# io-board-e-1.net
KiCad netlist of a schematic drawn in EAGLE
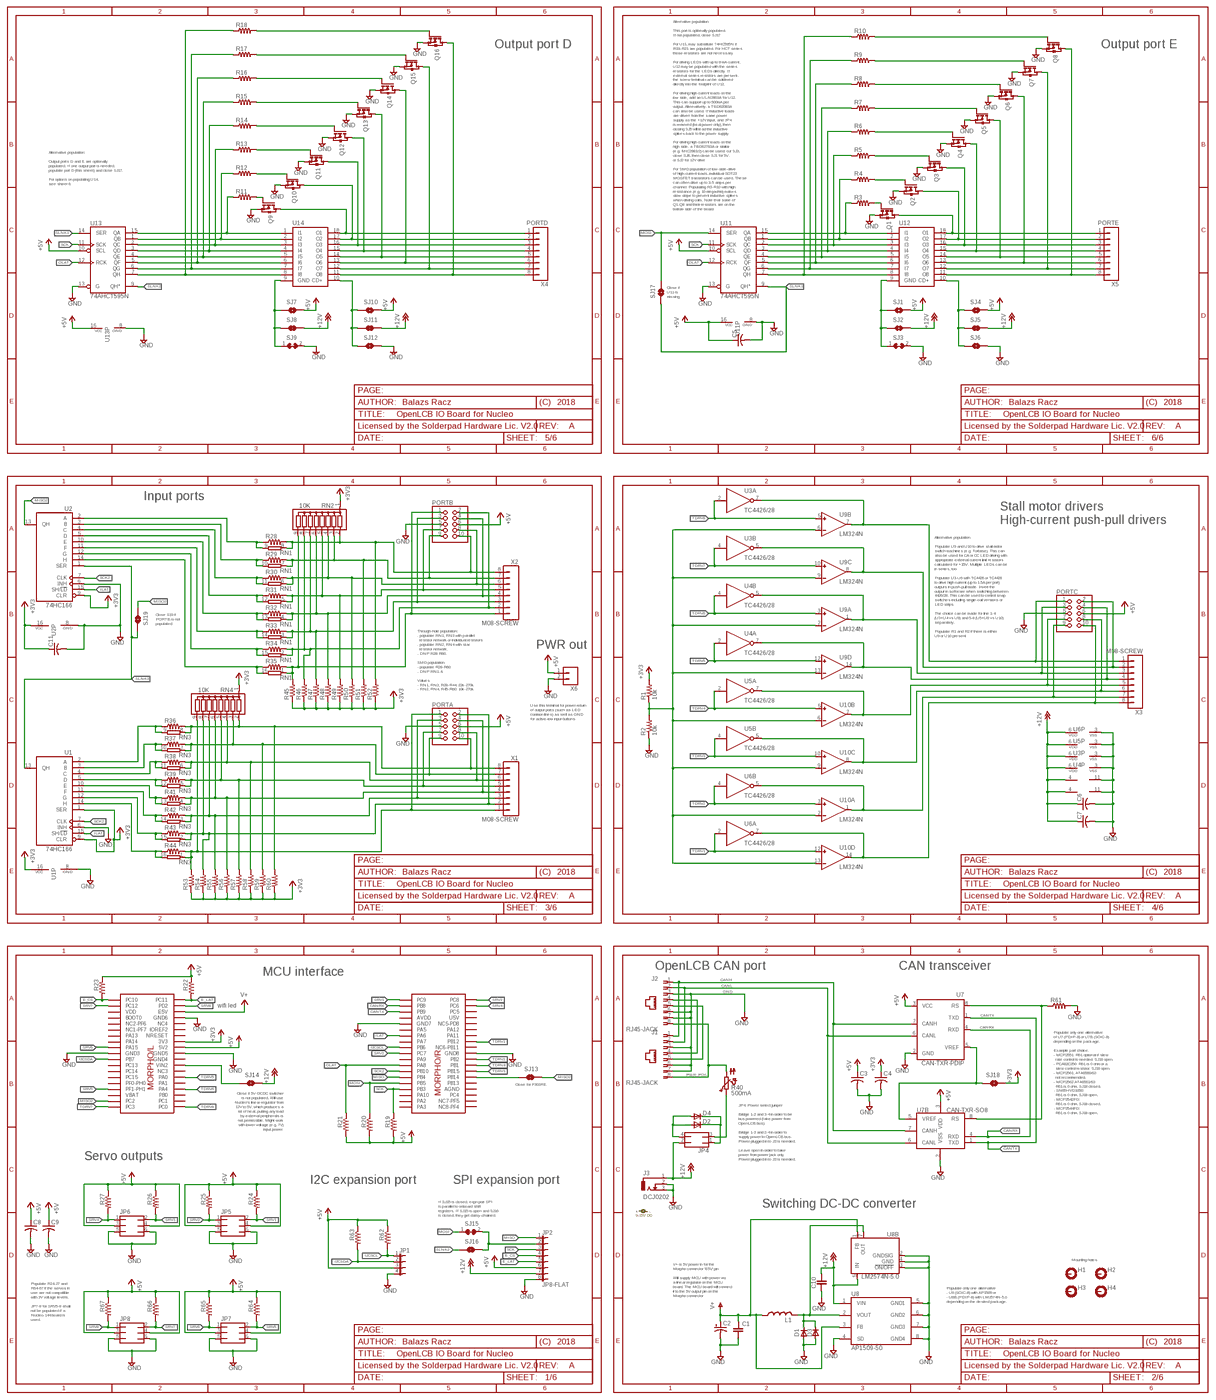
[diagram p0: schematic, sheet 1, overview]
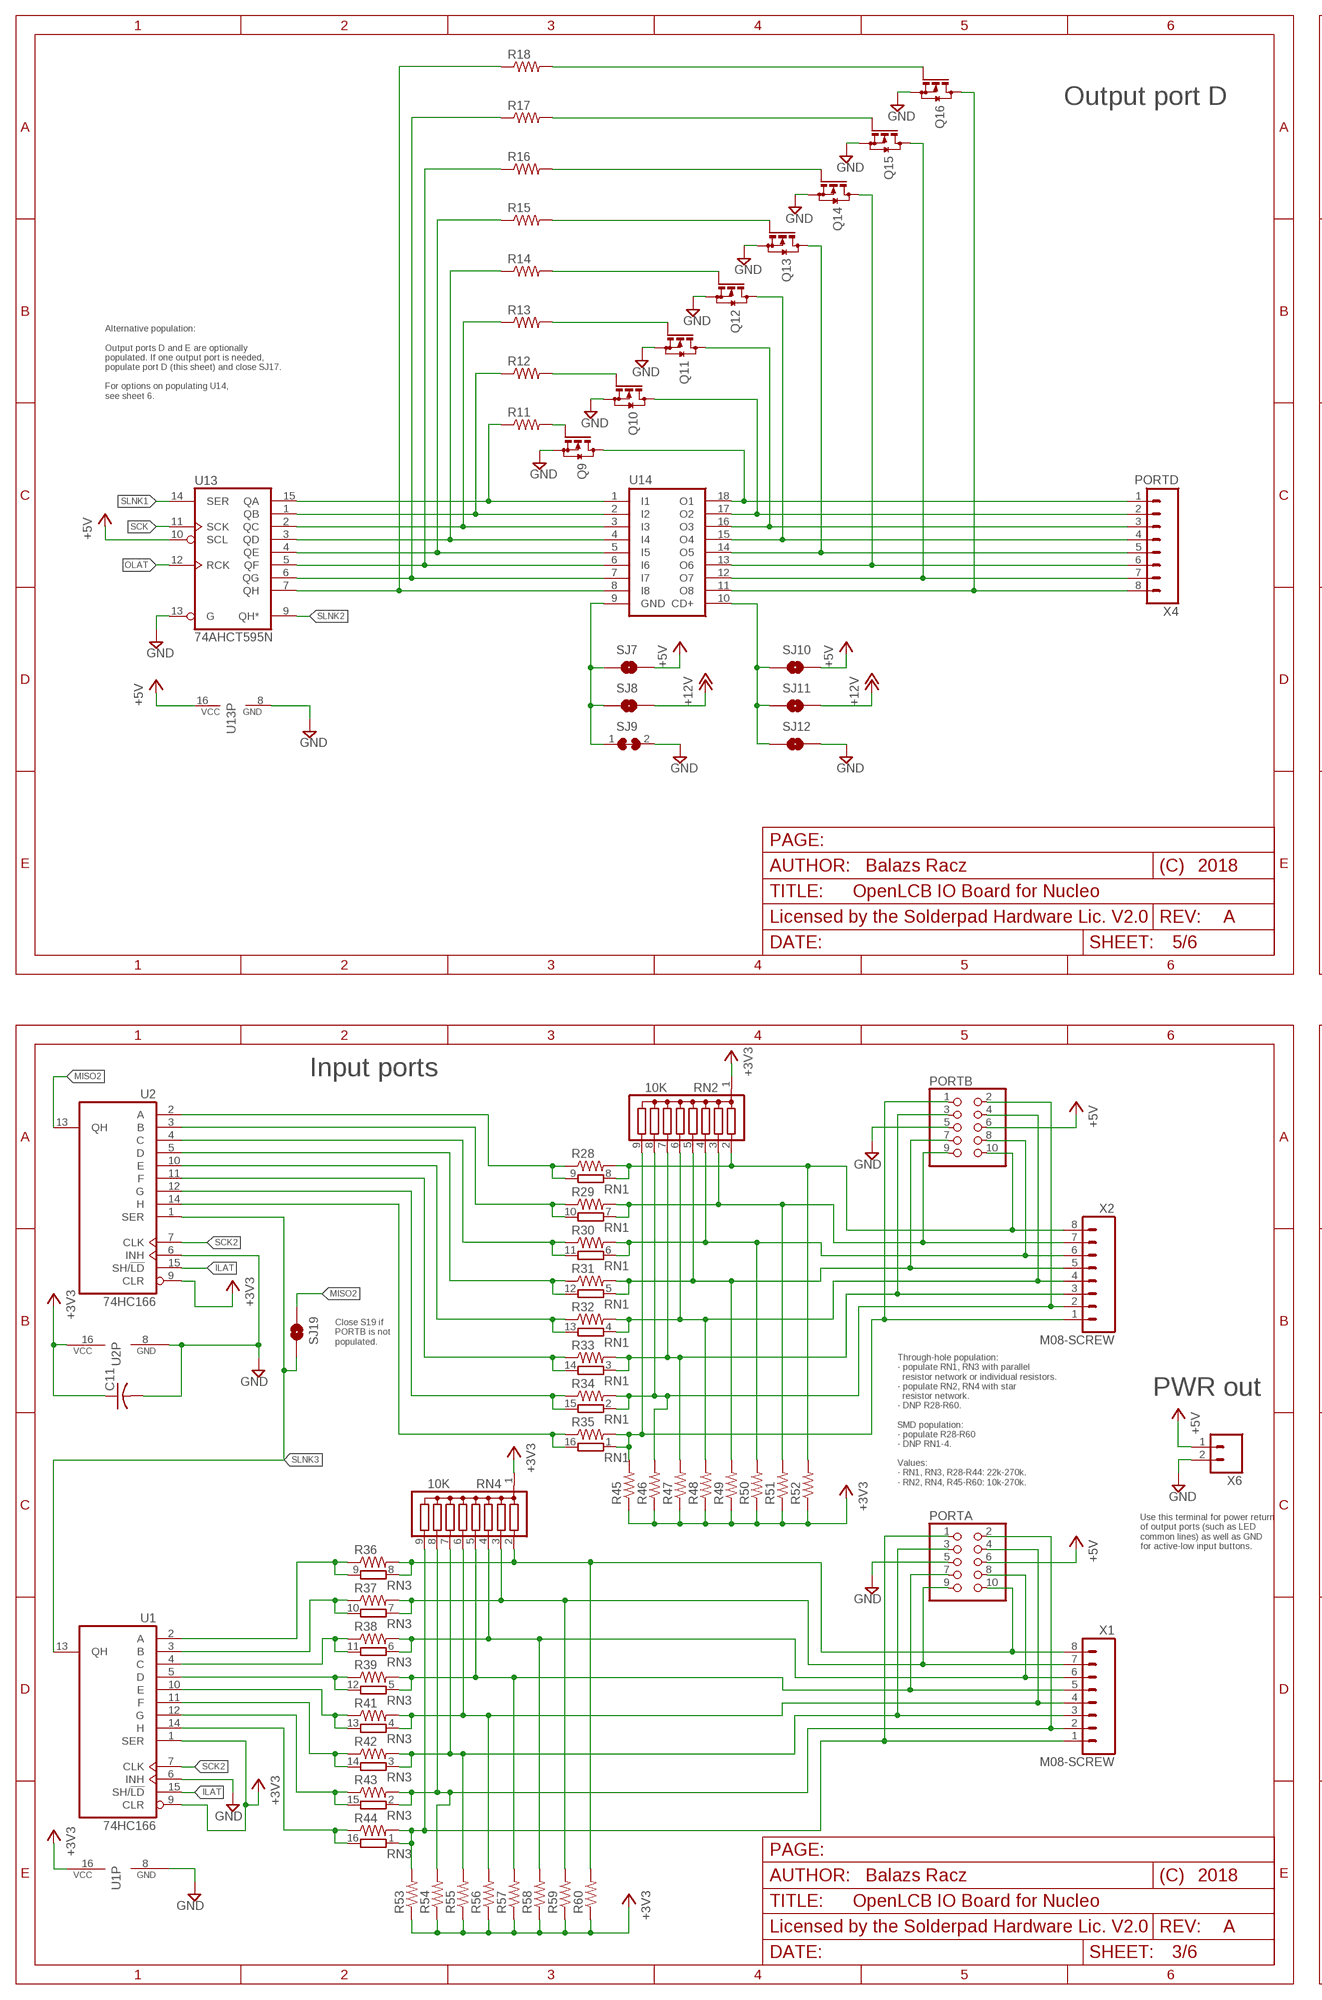
[diagram p1: schematic, sheet 1, part 1 of 4]
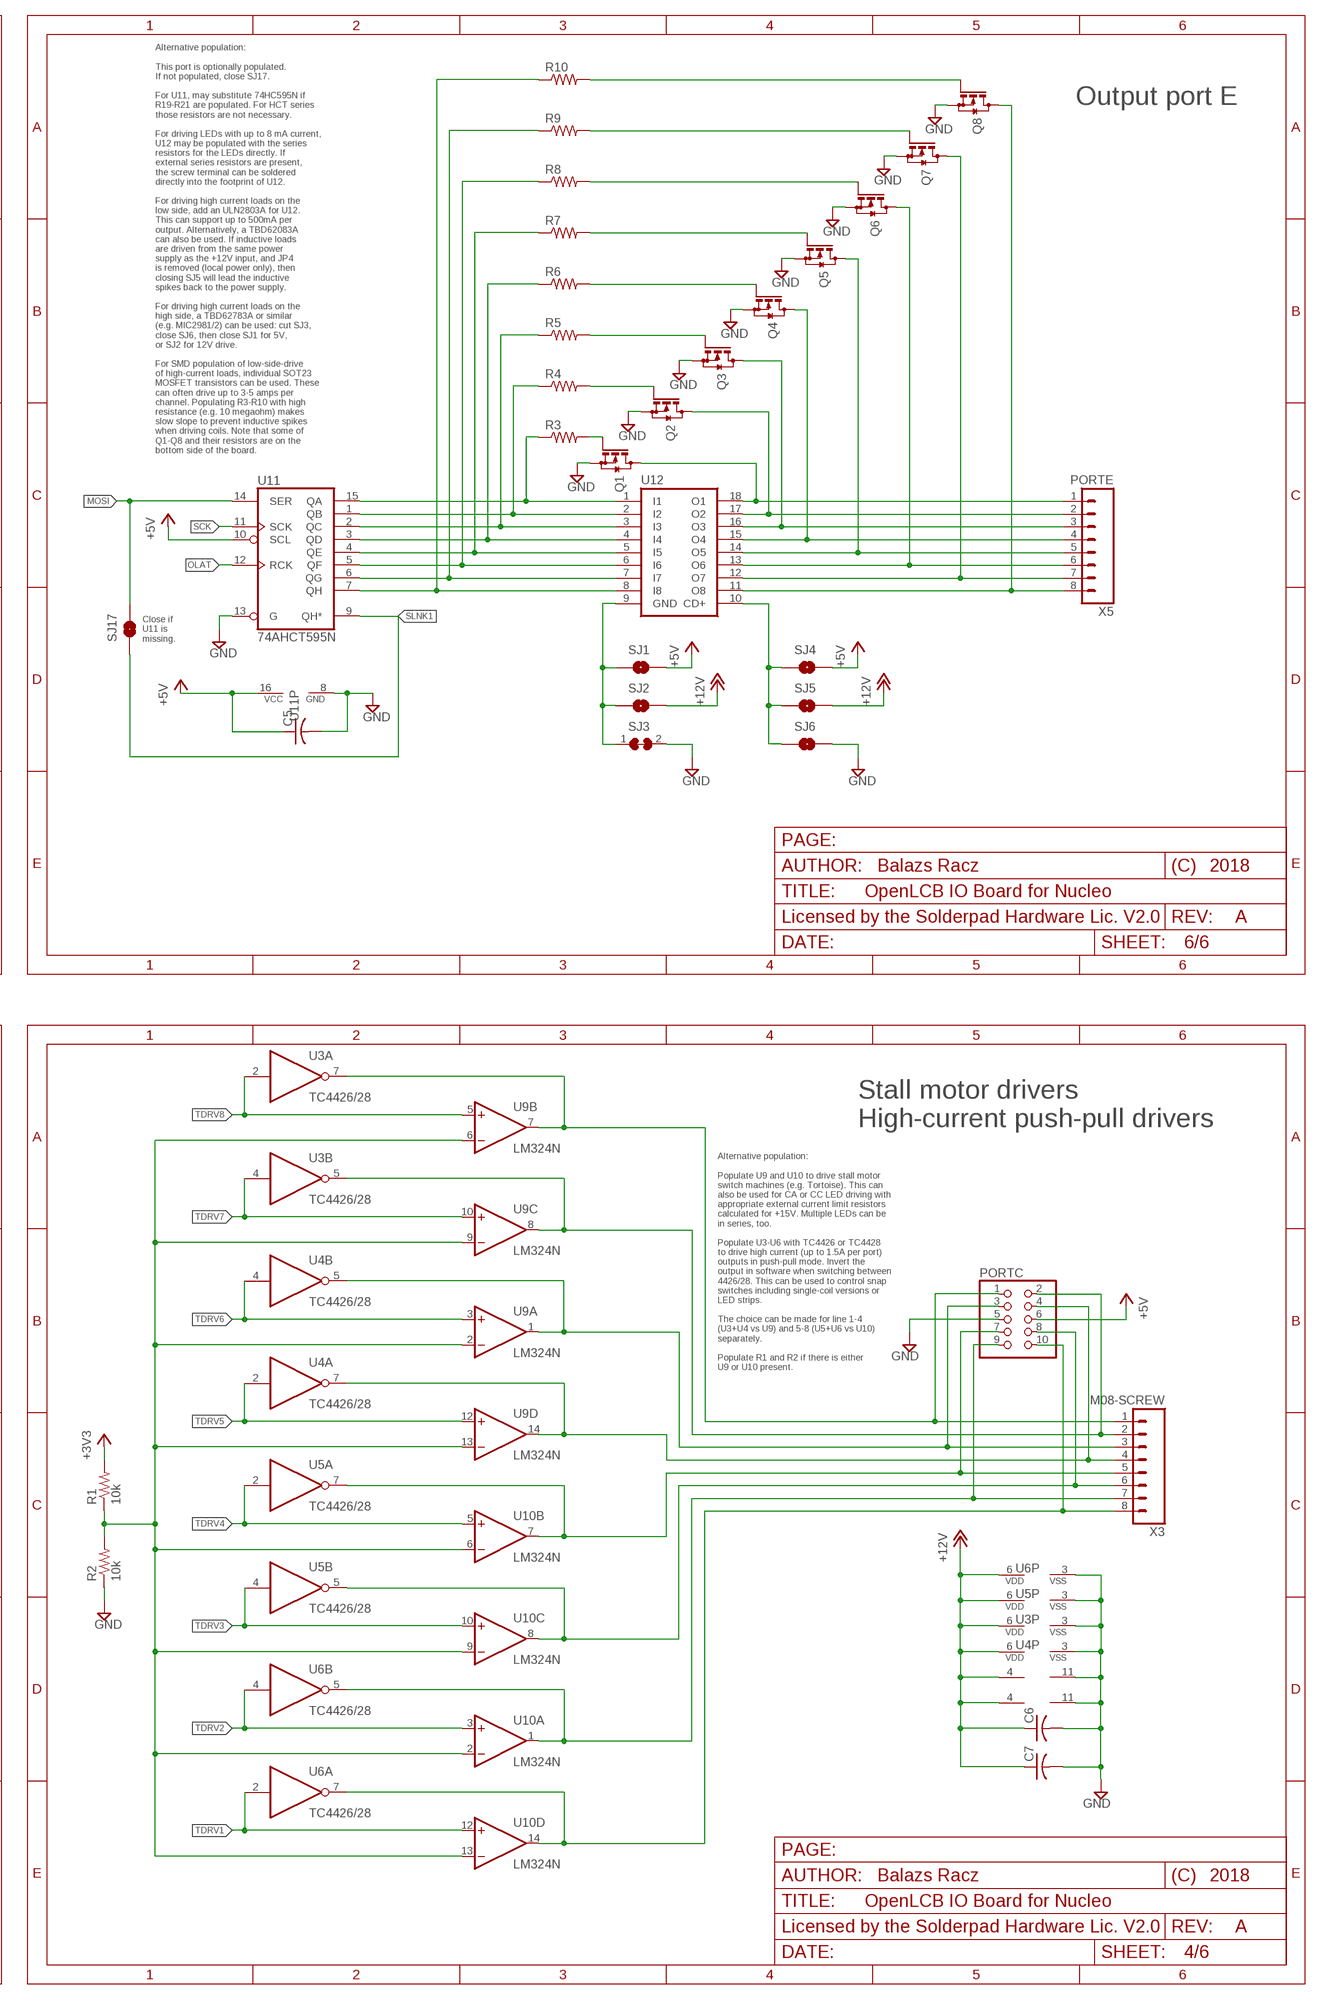
[diagram p2: schematic, sheet 1, part 2 of 4]
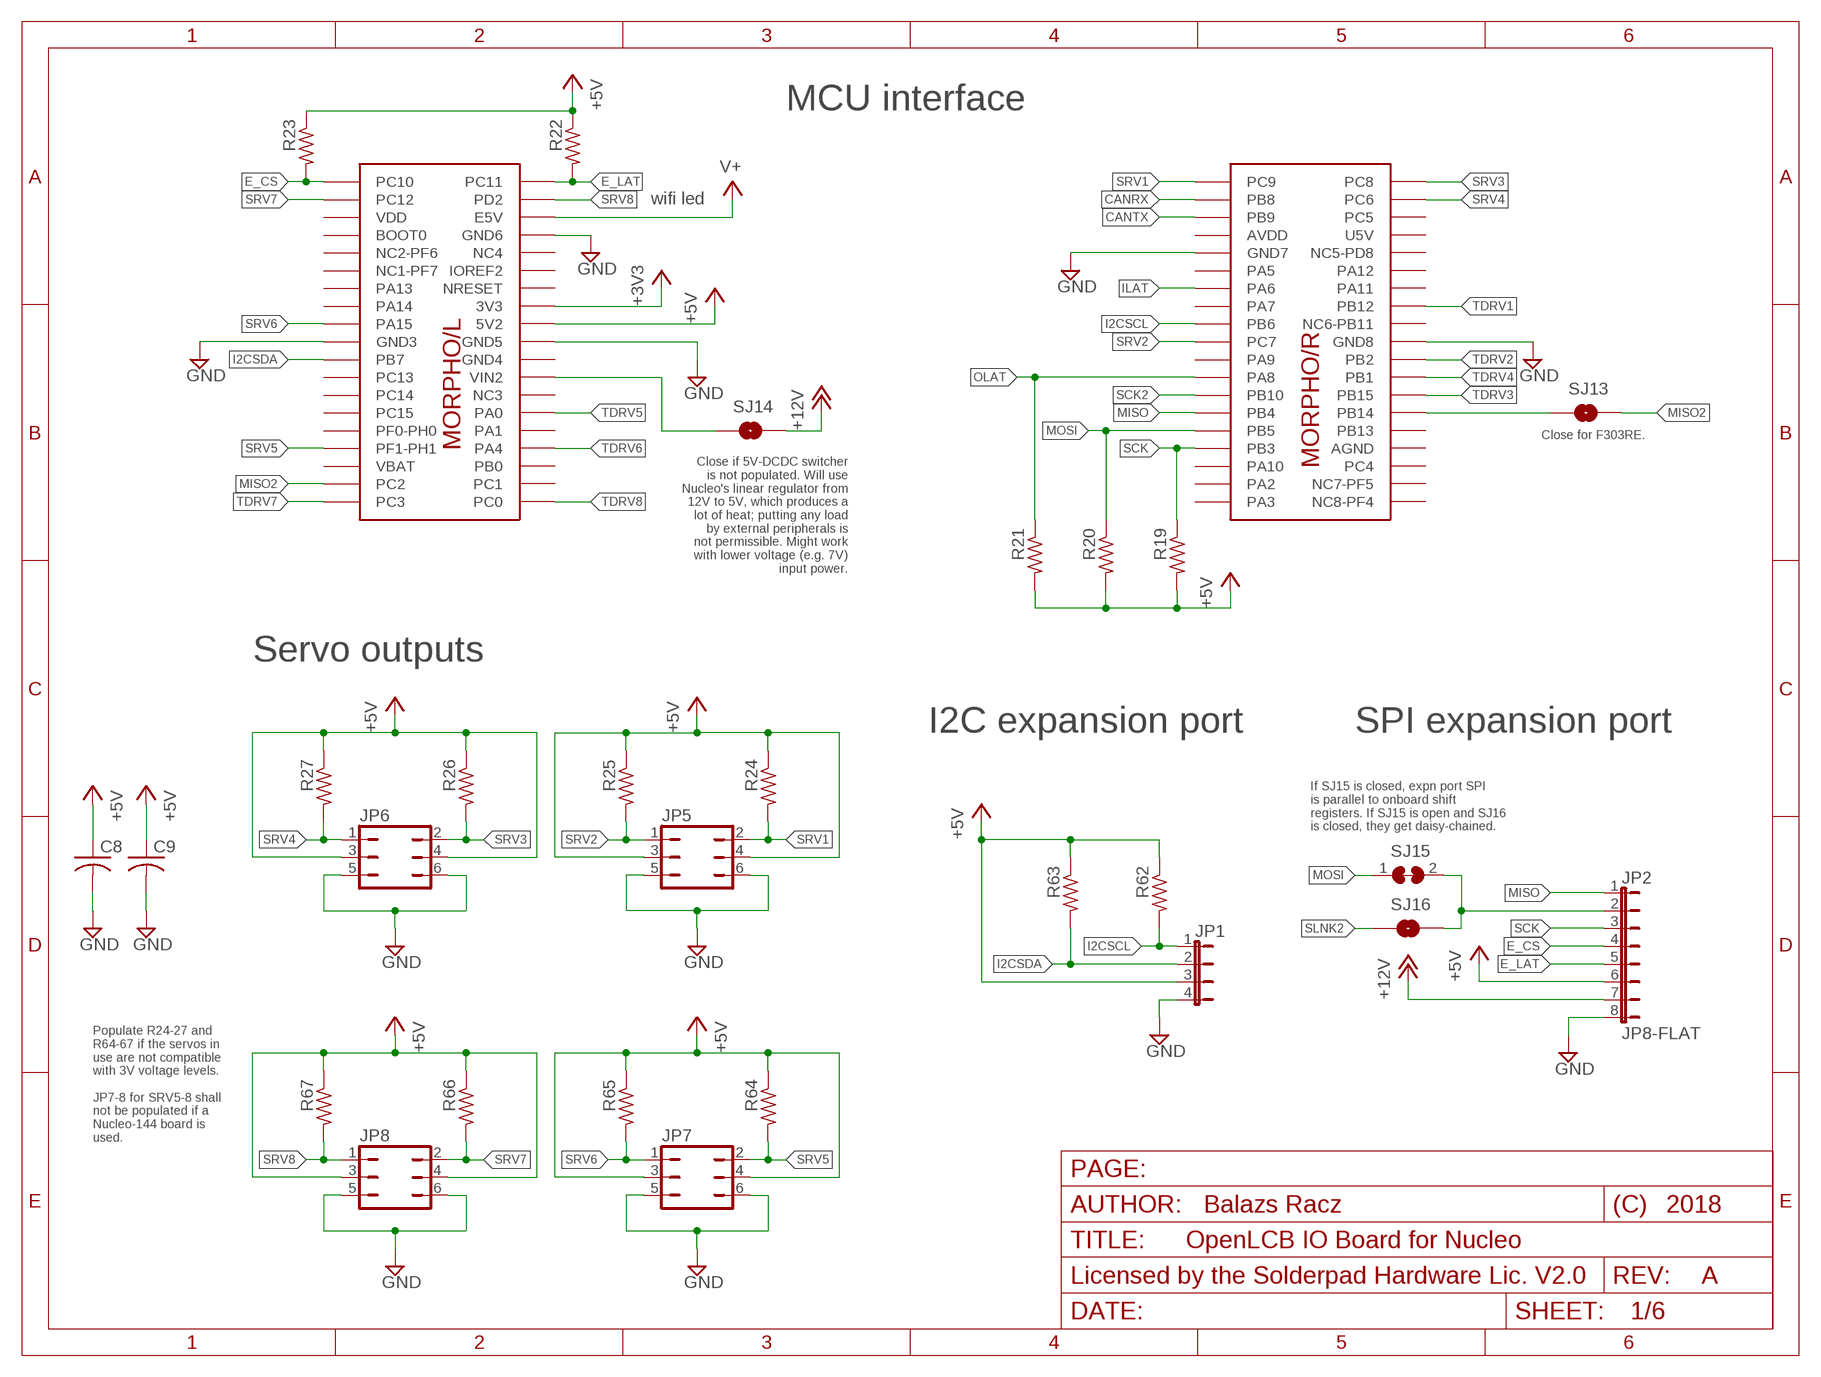
[diagram p3: schematic, sheet 1, part 3 of 4]
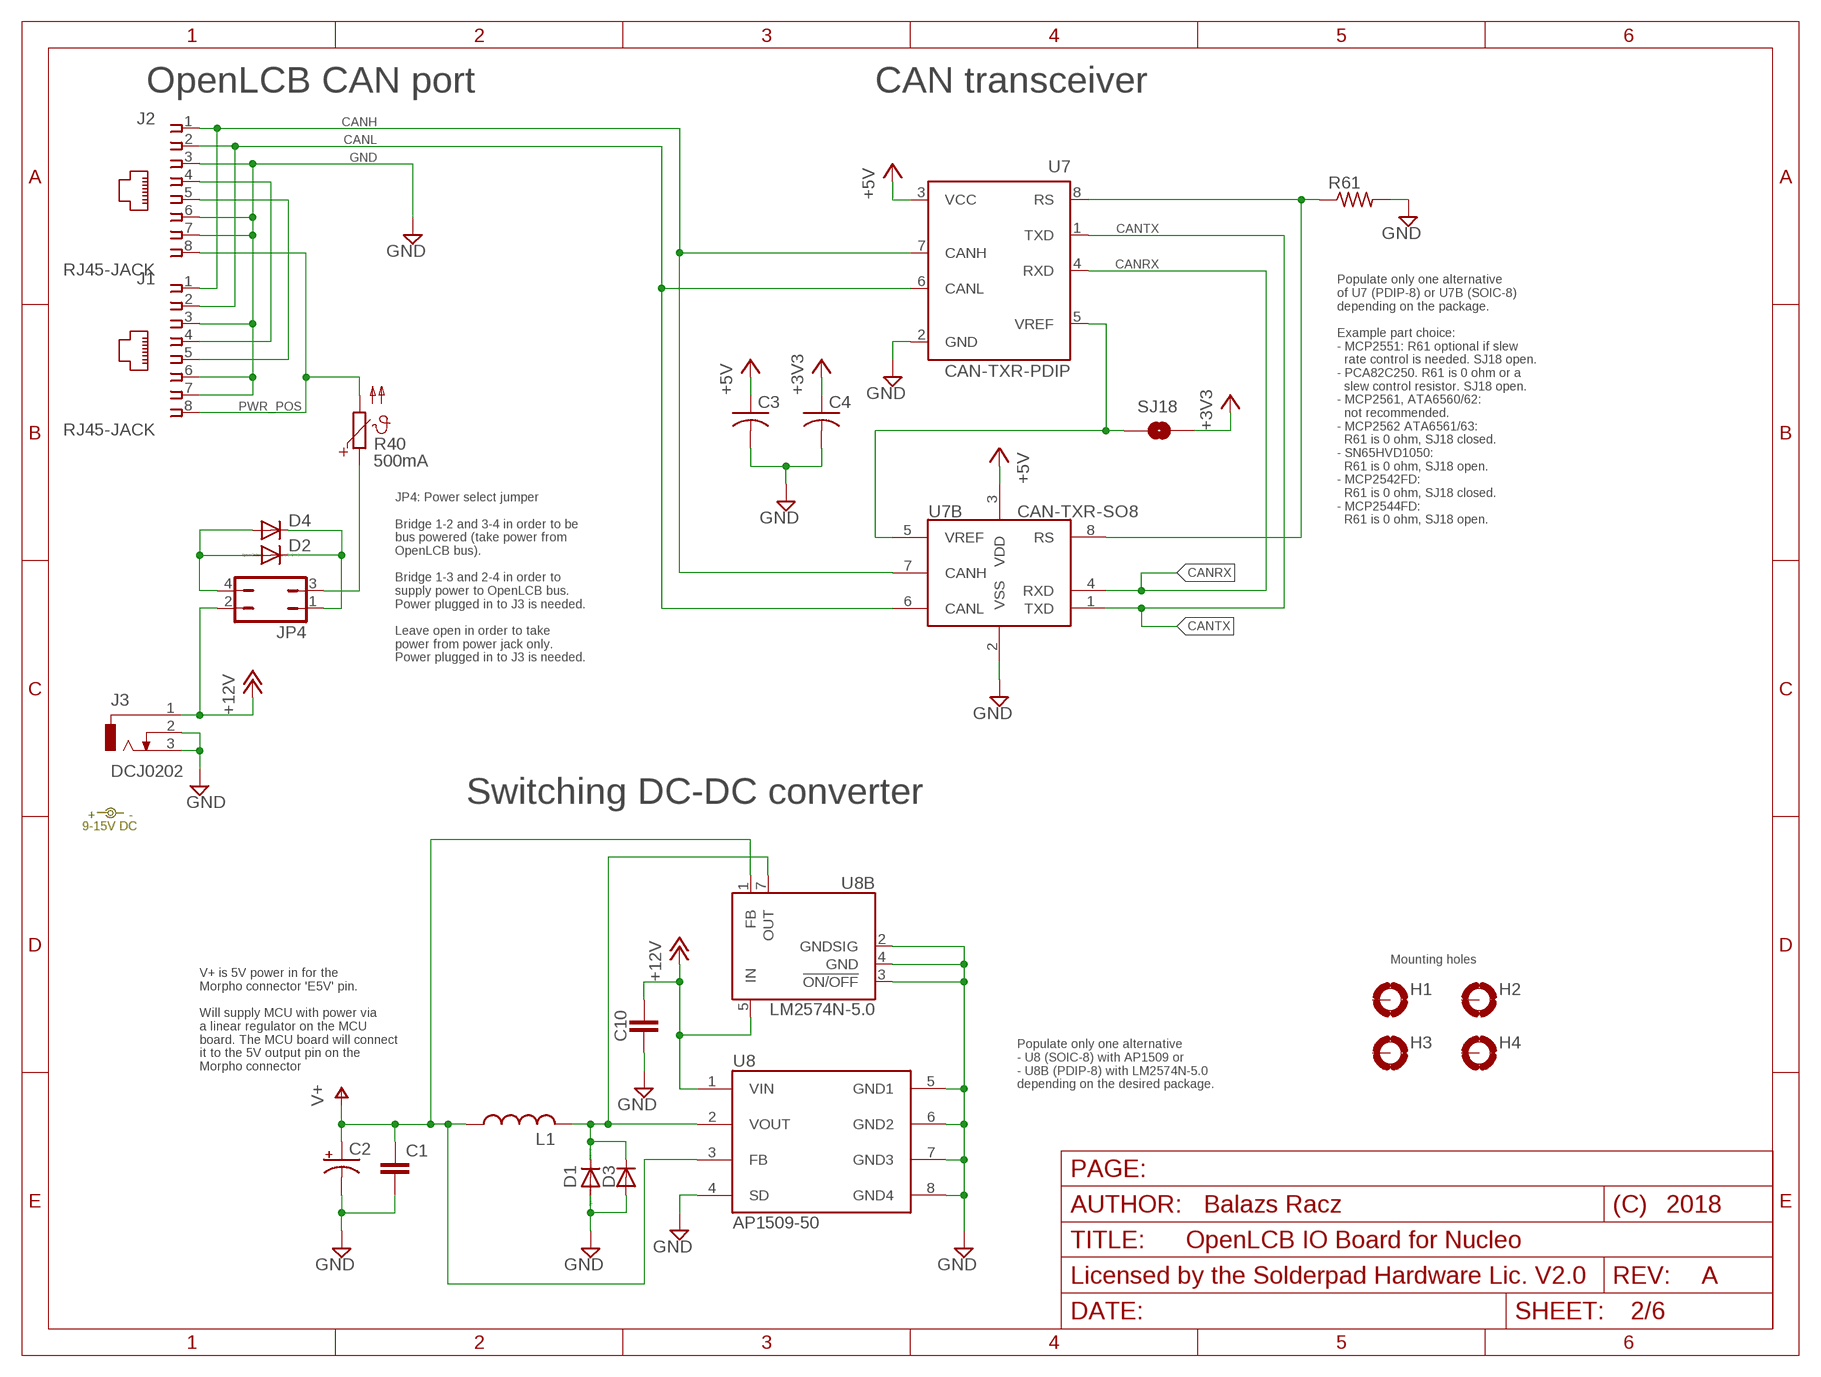
[diagram p4: schematic, sheet 1, part 4 of 4]

(export (version "E")
  (design (tool "Eeschema 10.0.6"))
  (components
    (comp (ref "+12V")
      (value "9-15V DC")
      (footprint "eagle-import:POWER_USAGE")
      (libsource (lib "eagle-import") (part "DOC-POWER_LABEL"))
    )
    (comp (ref "C1")
      (value "C-EUC1206")
      (footprint "eagle-import:C1206")
      (libsource (lib "eagle-import") (part "C-EUC1206"))
    )
    (comp (ref "C2")
      (value "CPOL-USE2.5-5")
      (footprint "eagle-import:E2,5-5")
      (libsource (lib "eagle-import") (part "CPOL-USE2.5-5"))
    )
    (comp (ref "C3")
      (value "C-USC0805")
      (footprint "eagle-import:C0805")
      (libsource (lib "eagle-import") (part "C-USC0805"))
    )
    (comp (ref "C4")
      (value "C-USC0805")
      (footprint "eagle-import:C0805")
      (libsource (lib "eagle-import") (part "C-USC0805"))
    )
    (comp (ref "C5")
      (value "C-USC0805")
      (footprint "eagle-import:C0805")
      (libsource (lib "eagle-import") (part "C-USC0805"))
    )
    (comp (ref "C6")
      (value "C-USC1206")
      (footprint "eagle-import:C1206")
      (libsource (lib "eagle-import") (part "C-USC1206"))
    )
    (comp (ref "C7")
      (value "C-USC1206")
      (footprint "eagle-import:C1206")
      (libsource (lib "eagle-import") (part "C-USC1206"))
    )
    (comp (ref "C8")
      (value "C-USC1206")
      (footprint "eagle-import:C1206")
      (libsource (lib "eagle-import") (part "C-USC1206"))
    )
    (comp (ref "C9")
      (value "C-USC1206")
      (footprint "eagle-import:C1206")
      (libsource (lib "eagle-import") (part "C-USC1206"))
    )
    (comp (ref "C10")
      (value "C-EUC1206")
      (footprint "eagle-import:C1206")
      (libsource (lib "eagle-import") (part "C-EUC1206"))
    )
    (comp (ref "C11")
      (value "C-USC0805")
      (footprint "eagle-import:C0805")
      (libsource (lib "eagle-import") (part "C-USC0805"))
    )
    (comp (ref "D1")
      (value "DIODE-DO41-7.6")
      (footprint "eagle-import:DO41-7.6")
      (libsource (lib "eagle-import") (part "DIODE-DO41-7.6"))
    )
    (comp (ref "D2")
      (value "DIODE-DO41-7.6")
      (footprint "eagle-import:DO41-7.6")
      (libsource (lib "eagle-import") (part "DIODE-DO41-7.6"))
    )
    (comp (ref "D3")
      (value "DIODEDO-214AA-NODOC")
      (footprint "eagle-import:DO214AA-NODOC")
      (libsource (lib "eagle-import") (part "DIODEDO-214AA-NODOC"))
    )
    (comp (ref "D4")
      (value "DIODEDO-214AA-NODOC")
      (footprint "eagle-import:DO214AA-NODOC")
      (libsource (lib "eagle-import") (part "DIODEDO-214AA-NODOC"))
    )
    (comp (ref "H1")
      (value "MOUNT-PAD-ROUND3.3")
      (footprint "eagle-import:3,3-PAD")
      (libsource (lib "eagle-import") (part "MOUNT-PAD-ROUND3.3"))
    )
    (comp (ref "H2")
      (value "MOUNT-PAD-ROUND3.3")
      (footprint "eagle-import:3,3-PAD")
      (libsource (lib "eagle-import") (part "MOUNT-PAD-ROUND3.3"))
    )
    (comp (ref "H3")
      (value "MOUNT-PAD-ROUND3.3")
      (footprint "eagle-import:3,3-PAD")
      (libsource (lib "eagle-import") (part "MOUNT-PAD-ROUND3.3"))
    )
    (comp (ref "H4")
      (value "MOUNT-PAD-ROUND3.3")
      (footprint "eagle-import:3,3-PAD")
      (libsource (lib "eagle-import") (part "MOUNT-PAD-ROUND3.3"))
    )
    (comp (ref "J1")
      (value "RJ45-JACK")
      (footprint "eagle-import:RJ45-PULSE-E5J88")
      (libsource (lib "eagle-import") (part "RJ45-JACKRJ45-PULSE-E5J00"))
    )
    (comp (ref "J2")
      (value "RJ45-JACK")
      (footprint "eagle-import:RJ45-PULSE-E5J88")
      (libsource (lib "eagle-import") (part "RJ45-JACKRJ45-PULSE-E5J00"))
    )
    (comp (ref "J3")
      (value "DCJ0202")
      (footprint "eagle-import:DCJ0202")
      (libsource (lib "eagle-import") (part "DCJ0202"))
    )
    (comp (ref "JP1")
      (value "JP4-FLAT")
      (footprint "eagle-import:JP4F")
      (libsource (lib "eagle-import") (part "JP4-FLAT"))
    )
    (comp (ref "JP2")
      (value "JP8-FLAT")
      (footprint "eagle-import:JP8F")
      (libsource (lib "eagle-import") (part "JP8-FLAT"))
    )
    (comp (ref "JP4")
      (value "JP2Q")
      (footprint "eagle-import:JP2Q")
      (libsource (lib "eagle-import") (part "JP2Q"))
    )
    (comp (ref "JP5")
      (value "JP3Q")
      (footprint "eagle-import:JP3Q")
      (libsource (lib "eagle-import") (part "JP3Q"))
    )
    (comp (ref "JP6")
      (value "JP3Q")
      (footprint "eagle-import:JP3Q")
      (libsource (lib "eagle-import") (part "JP3Q"))
    )
    (comp (ref "JP7")
      (value "JP3Q")
      (footprint "eagle-import:JP3Q")
      (libsource (lib "eagle-import") (part "JP3Q"))
    )
    (comp (ref "JP8")
      (value "JP3Q")
      (footprint "eagle-import:JP3Q")
      (libsource (lib "eagle-import") (part "JP3Q"))
    )
    (comp (ref "L1")
      (value "L-US")
      (footprint "eagle-import:L5-8,5")
      (libsource (lib "eagle-import") (part "L-US"))
    )
    (comp (ref "PORTA")
      (value "PINHD-2X5CN")
      (footprint "eagle-import:CON10M")
      (libsource (lib "eagle-import") (part "PINHD-2X5CN"))
    )
    (comp (ref "PORTB")
      (value "PINHD-2X5CN")
      (footprint "eagle-import:CON10M")
      (libsource (lib "eagle-import") (part "PINHD-2X5CN"))
    )
    (comp (ref "PORTC")
      (value "PINHD-2X5CN")
      (footprint "eagle-import:CON10M")
      (libsource (lib "eagle-import") (part "PINHD-2X5CN"))
    )
    (comp (ref "Q1")
      (value "BSS123")
      (footprint "eagle-import:SOT23")
      (libsource (lib "eagle-import") (part "BSS123"))
    )
    (comp (ref "Q2")
      (value "BSS123")
      (footprint "eagle-import:SOT23")
      (libsource (lib "eagle-import") (part "BSS123"))
    )
    (comp (ref "Q3")
      (value "BSS123")
      (footprint "eagle-import:SOT23")
      (libsource (lib "eagle-import") (part "BSS123"))
    )
    (comp (ref "Q4")
      (value "BSS123")
      (footprint "eagle-import:SOT23")
      (libsource (lib "eagle-import") (part "BSS123"))
    )
    (comp (ref "Q5")
      (value "BSS123")
      (footprint "eagle-import:SOT23")
      (libsource (lib "eagle-import") (part "BSS123"))
    )
    (comp (ref "Q6")
      (value "BSS123")
      (footprint "eagle-import:SOT23")
      (libsource (lib "eagle-import") (part "BSS123"))
    )
    (comp (ref "Q7")
      (value "BSS123")
      (footprint "eagle-import:SOT23")
      (libsource (lib "eagle-import") (part "BSS123"))
    )
    (comp (ref "Q8")
      (value "BSS123")
      (footprint "eagle-import:SOT23")
      (libsource (lib "eagle-import") (part "BSS123"))
    )
    (comp (ref "Q9")
      (value "BSS123")
      (footprint "eagle-import:SOT23")
      (libsource (lib "eagle-import") (part "BSS123"))
    )
    (comp (ref "Q10")
      (value "BSS123")
      (footprint "eagle-import:SOT23")
      (libsource (lib "eagle-import") (part "BSS123"))
    )
    (comp (ref "Q11")
      (value "BSS123")
      (footprint "eagle-import:SOT23")
      (libsource (lib "eagle-import") (part "BSS123"))
    )
    (comp (ref "Q12")
      (value "BSS123")
      (footprint "eagle-import:SOT23")
      (libsource (lib "eagle-import") (part "BSS123"))
    )
    (comp (ref "Q13")
      (value "BSS123")
      (footprint "eagle-import:SOT23")
      (libsource (lib "eagle-import") (part "BSS123"))
    )
    (comp (ref "Q14")
      (value "BSS123")
      (footprint "eagle-import:SOT23")
      (libsource (lib "eagle-import") (part "BSS123"))
    )
    (comp (ref "Q15")
      (value "BSS123")
      (footprint "eagle-import:SOT23")
      (libsource (lib "eagle-import") (part "BSS123"))
    )
    (comp (ref "Q16")
      (value "BSS123")
      (footprint "eagle-import:SOT23")
      (libsource (lib "eagle-import") (part "BSS123"))
    )
    (comp (ref "R1")
      (value "10k")
      (footprint "eagle-import:R0805")
      (libsource (lib "eagle-import") (part "R-US_R0805"))
    )
    (comp (ref "R2")
      (value "10k")
      (footprint "eagle-import:R0805")
      (libsource (lib "eagle-import") (part "R-US_R0805"))
    )
    (comp (ref "R3")
      (value "R-US_R0603")
      (footprint "eagle-import:R0603")
      (libsource (lib "eagle-import") (part "R-US_R0603"))
    )
    (comp (ref "R4")
      (value "R-US_R0603")
      (footprint "eagle-import:R0603")
      (libsource (lib "eagle-import") (part "R-US_R0603"))
    )
    (comp (ref "R5")
      (value "R-US_R0603")
      (footprint "eagle-import:R0603")
      (libsource (lib "eagle-import") (part "R-US_R0603"))
    )
    (comp (ref "R6")
      (value "R-US_R0603")
      (footprint "eagle-import:R0603")
      (libsource (lib "eagle-import") (part "R-US_R0603"))
    )
    (comp (ref "R7")
      (value "R-US_R0603")
      (footprint "eagle-import:R0603")
      (libsource (lib "eagle-import") (part "R-US_R0603"))
    )
    (comp (ref "R8")
      (value "R-US_R0603")
      (footprint "eagle-import:R0603")
      (libsource (lib "eagle-import") (part "R-US_R0603"))
    )
    (comp (ref "R9")
      (value "R-US_R0603")
      (footprint "eagle-import:R0603")
      (libsource (lib "eagle-import") (part "R-US_R0603"))
    )
    (comp (ref "R10")
      (value "R-US_R0603")
      (footprint "eagle-import:R0603")
      (libsource (lib "eagle-import") (part "R-US_R0603"))
    )
    (comp (ref "R11")
      (value "R-US_R0603")
      (footprint "eagle-import:R0603")
      (libsource (lib "eagle-import") (part "R-US_R0603"))
    )
    (comp (ref "R12")
      (value "R-US_R0603")
      (footprint "eagle-import:R0603")
      (libsource (lib "eagle-import") (part "R-US_R0603"))
    )
    (comp (ref "R13")
      (value "R-US_R0603")
      (footprint "eagle-import:R0603")
      (libsource (lib "eagle-import") (part "R-US_R0603"))
    )
    (comp (ref "R14")
      (value "R-US_R0603")
      (footprint "eagle-import:R0603")
      (libsource (lib "eagle-import") (part "R-US_R0603"))
    )
    (comp (ref "R15")
      (value "R-US_R0603")
      (footprint "eagle-import:R0603")
      (libsource (lib "eagle-import") (part "R-US_R0603"))
    )
    (comp (ref "R16")
      (value "R-US_R0603")
      (footprint "eagle-import:R0603")
      (libsource (lib "eagle-import") (part "R-US_R0603"))
    )
    (comp (ref "R17")
      (value "R-US_R0603")
      (footprint "eagle-import:R0603")
      (libsource (lib "eagle-import") (part "R-US_R0603"))
    )
    (comp (ref "R18")
      (value "R-US_R0603")
      (footprint "eagle-import:R0603")
      (libsource (lib "eagle-import") (part "R-US_R0603"))
    )
    (comp (ref "R19")
      (value "R-US_R0805")
      (footprint "eagle-import:R0805")
      (libsource (lib "eagle-import") (part "rcl_334_R-US_R0805"))
    )
    (comp (ref "R20")
      (value "R-US_R0805")
      (footprint "eagle-import:R0805")
      (libsource (lib "eagle-import") (part "rcl_334_R-US_R0805"))
    )
    (comp (ref "R21")
      (value "R-US_R0805")
      (footprint "eagle-import:R0805")
      (libsource (lib "eagle-import") (part "rcl_334_R-US_R0805"))
    )
    (comp (ref "R22")
      (value "R-US_R0805")
      (footprint "eagle-import:R0805")
      (libsource (lib "eagle-import") (part "rcl_334_R-US_R0805"))
    )
    (comp (ref "R23")
      (value "R-US_R0805")
      (footprint "eagle-import:R0805")
      (libsource (lib "eagle-import") (part "rcl_334_R-US_R0805"))
    )
    (comp (ref "R24")
      (value "R-US_R0805")
      (footprint "eagle-import:R0805")
      (libsource (lib "eagle-import") (part "rcl_334_R-US_R0805"))
    )
    (comp (ref "R25")
      (value "R-US_R0805")
      (footprint "eagle-import:R0805")
      (libsource (lib "eagle-import") (part "rcl_334_R-US_R0805"))
    )
    (comp (ref "R26")
      (value "R-US_R0805")
      (footprint "eagle-import:R0805")
      (libsource (lib "eagle-import") (part "rcl_334_R-US_R0805"))
    )
    (comp (ref "R27")
      (value "R-US_R0805")
      (footprint "eagle-import:R0805")
      (libsource (lib "eagle-import") (part "rcl_334_R-US_R0805"))
    )
    (comp (ref "R28")
      (value "R-US_R0603")
      (footprint "eagle-import:R0603")
      (libsource (lib "eagle-import") (part "rcl_334_R-US_R0603"))
    )
    (comp (ref "R29")
      (value "R-US_R0603")
      (footprint "eagle-import:R0603")
      (libsource (lib "eagle-import") (part "rcl_334_R-US_R0603"))
    )
    (comp (ref "R30")
      (value "R-US_R0603")
      (footprint "eagle-import:R0603")
      (libsource (lib "eagle-import") (part "rcl_334_R-US_R0603"))
    )
    (comp (ref "R31")
      (value "R-US_R0603")
      (footprint "eagle-import:R0603")
      (libsource (lib "eagle-import") (part "rcl_334_R-US_R0603"))
    )
    (comp (ref "R32")
      (value "R-US_R0603")
      (footprint "eagle-import:R0603")
      (libsource (lib "eagle-import") (part "rcl_334_R-US_R0603"))
    )
    (comp (ref "R33")
      (value "R-US_R0603")
      (footprint "eagle-import:R0603")
      (libsource (lib "eagle-import") (part "rcl_334_R-US_R0603"))
    )
    (comp (ref "R34")
      (value "R-US_R0603")
      (footprint "eagle-import:R0603")
      (libsource (lib "eagle-import") (part "rcl_334_R-US_R0603"))
    )
    (comp (ref "R35")
      (value "R-US_R0603")
      (footprint "eagle-import:R0603")
      (libsource (lib "eagle-import") (part "rcl_334_R-US_R0603"))
    )
    (comp (ref "R36")
      (value "R-US_R0603")
      (footprint "eagle-import:R0603")
      (libsource (lib "eagle-import") (part "rcl_334_R-US_R0603"))
    )
    (comp (ref "R37")
      (value "R-US_R0603")
      (footprint "eagle-import:R0603")
      (libsource (lib "eagle-import") (part "rcl_334_R-US_R0603"))
    )
    (comp (ref "R38")
      (value "R-US_R0603")
      (footprint "eagle-import:R0603")
      (libsource (lib "eagle-import") (part "rcl_334_R-US_R0603"))
    )
    (comp (ref "R39")
      (value "R-US_R0603")
      (footprint "eagle-import:R0603")
      (libsource (lib "eagle-import") (part "rcl_334_R-US_R0603"))
    )
    (comp (ref "R40")
      (value "500mA")
      (footprint "eagle-import:PTC1812")
      (libsource (lib "eagle-import") (part "PTC_1812"))
    )
    (comp (ref "R41")
      (value "R-US_R0603")
      (footprint "eagle-import:R0603")
      (libsource (lib "eagle-import") (part "rcl_334_R-US_R0603"))
    )
    (comp (ref "R42")
      (value "R-US_R0603")
      (footprint "eagle-import:R0603")
      (libsource (lib "eagle-import") (part "rcl_334_R-US_R0603"))
    )
    (comp (ref "R43")
      (value "R-US_R0603")
      (footprint "eagle-import:R0603")
      (libsource (lib "eagle-import") (part "rcl_334_R-US_R0603"))
    )
    (comp (ref "R44")
      (value "R-US_R0603")
      (footprint "eagle-import:R0603")
      (libsource (lib "eagle-import") (part "rcl_334_R-US_R0603"))
    )
    (comp (ref "R45")
      (value "R-US")
      (footprint "eagle-import:R0603")
      (libsource (lib "eagle-import") (part "R-US"))
    )
    (comp (ref "R46")
      (value "R-US")
      (footprint "eagle-import:R0603")
      (libsource (lib "eagle-import") (part "R-US"))
    )
    (comp (ref "R47")
      (value "R-US")
      (footprint "eagle-import:R0603")
      (libsource (lib "eagle-import") (part "R-US"))
    )
    (comp (ref "R48")
      (value "R-US")
      (footprint "eagle-import:R0603")
      (libsource (lib "eagle-import") (part "R-US"))
    )
    (comp (ref "R49")
      (value "R-US")
      (footprint "eagle-import:R0603")
      (libsource (lib "eagle-import") (part "R-US"))
    )
    (comp (ref "R50")
      (value "R-US")
      (footprint "eagle-import:R0603")
      (libsource (lib "eagle-import") (part "R-US"))
    )
    (comp (ref "R51")
      (value "R-US")
      (footprint "eagle-import:R0603")
      (libsource (lib "eagle-import") (part "R-US"))
    )
    (comp (ref "R52")
      (value "R-US")
      (footprint "eagle-import:R0603")
      (libsource (lib "eagle-import") (part "R-US"))
    )
    (comp (ref "R53")
      (value "R-US")
      (footprint "eagle-import:R0603")
      (libsource (lib "eagle-import") (part "R-US"))
    )
    (comp (ref "R54")
      (value "R-US")
      (footprint "eagle-import:R0603")
      (libsource (lib "eagle-import") (part "R-US"))
    )
    (comp (ref "R55")
      (value "R-US")
      (footprint "eagle-import:R0603")
      (libsource (lib "eagle-import") (part "R-US"))
    )
    (comp (ref "R56")
      (value "R-US")
      (footprint "eagle-import:R0603")
      (libsource (lib "eagle-import") (part "R-US"))
    )
    (comp (ref "R57")
      (value "R-US")
      (footprint "eagle-import:R0603")
      (libsource (lib "eagle-import") (part "R-US"))
    )
    (comp (ref "R58")
      (value "R-US")
      (footprint "eagle-import:R0603")
      (libsource (lib "eagle-import") (part "R-US"))
    )
    (comp (ref "R59")
      (value "R-US")
      (footprint "eagle-import:R0603")
      (libsource (lib "eagle-import") (part "R-US"))
    )
    (comp (ref "R60")
      (value "R-US")
      (footprint "eagle-import:R0603")
      (libsource (lib "eagle-import") (part "R-US"))
    )
    (comp (ref "R61")
      (value "R-US_R0805")
      (footprint "eagle-import:R0805")
      (libsource (lib "eagle-import") (part "rcl_334_R-US_R0805"))
    )
    (comp (ref "R62")
      (value "R-US_R0805")
      (footprint "eagle-import:R0805")
      (libsource (lib "eagle-import") (part "rcl_334_R-US_R0805"))
    )
    (comp (ref "R63")
      (value "R-US_R0805")
      (footprint "eagle-import:R0805")
      (libsource (lib "eagle-import") (part "rcl_334_R-US_R0805"))
    )
    (comp (ref "R64")
      (value "R-US_R0805")
      (footprint "eagle-import:R0805")
      (libsource (lib "eagle-import") (part "rcl_334_R-US_R0805"))
    )
    (comp (ref "R65")
      (value "R-US_R0805")
      (footprint "eagle-import:R0805")
      (libsource (lib "eagle-import") (part "rcl_334_R-US_R0805"))
    )
    (comp (ref "R66")
      (value "R-US_R0805")
      (footprint "eagle-import:R0805")
      (libsource (lib "eagle-import") (part "rcl_334_R-US_R0805"))
    )
    (comp (ref "R67")
      (value "R-US_R0805")
      (footprint "eagle-import:R0805")
      (libsource (lib "eagle-import") (part "rcl_334_R-US_R0805"))
    )
    (comp (ref "RN1")
      (value "8R-P")
      (footprint "eagle-import:DIL16")
      (libsource (lib "eagle-import") (part "8R-P"))
    )
    (comp (ref "RN2")
      (value "10K")
      (footprint "eagle-import:SIL9")
      (libsource (lib "eagle-import") (part "G08R"))
    )
    (comp (ref "RN3")
      (value "8R-P")
      (footprint "eagle-import:DIL16")
      (libsource (lib "eagle-import") (part "8R-P"))
    )
    (comp (ref "RN4")
      (value "10K")
      (footprint "eagle-import:SIL9")
      (libsource (lib "eagle-import") (part "G08R"))
    )
    (comp (ref "SJ1")
      (value "SJRND2")
      (footprint "eagle-import:SJ_RND2")
      (libsource (lib "eagle-import") (part "SJRND2"))
    )
    (comp (ref "SJ2")
      (value "SJRND2")
      (footprint "eagle-import:SJ_RND2")
      (libsource (lib "eagle-import") (part "SJRND2"))
    )
    (comp (ref "SJ3")
      (value "SJ-C")
      (footprint "eagle-import:SJW-C")
      (libsource (lib "eagle-import") (part "SJ-C"))
    )
    (comp (ref "SJ4")
      (value "SJRND2")
      (footprint "eagle-import:SJ_RND2")
      (libsource (lib "eagle-import") (part "SJRND2"))
    )
    (comp (ref "SJ5")
      (value "SJRND2")
      (footprint "eagle-import:SJ_RND2")
      (libsource (lib "eagle-import") (part "SJRND2"))
    )
    (comp (ref "SJ6")
      (value "SJRND2")
      (footprint "eagle-import:SJ_RND2")
      (libsource (lib "eagle-import") (part "SJRND2"))
    )
    (comp (ref "SJ7")
      (value "SJRND2")
      (footprint "eagle-import:SJ_RND2")
      (libsource (lib "eagle-import") (part "SJRND2"))
    )
    (comp (ref "SJ8")
      (value "SJRND2")
      (footprint "eagle-import:SJ_RND2")
      (libsource (lib "eagle-import") (part "SJRND2"))
    )
    (comp (ref "SJ9")
      (value "SJ-C")
      (footprint "eagle-import:SJW-C")
      (libsource (lib "eagle-import") (part "SJ-C"))
    )
    (comp (ref "SJ10")
      (value "SJRND2")
      (footprint "eagle-import:SJ_RND2")
      (libsource (lib "eagle-import") (part "SJRND2"))
    )
    (comp (ref "SJ11")
      (value "SJRND2")
      (footprint "eagle-import:SJ_RND2")
      (libsource (lib "eagle-import") (part "SJRND2"))
    )
    (comp (ref "SJ12")
      (value "SJRND2")
      (footprint "eagle-import:SJ_RND2")
      (libsource (lib "eagle-import") (part "SJRND2"))
    )
    (comp (ref "SJ13")
      (value "SJRND2")
      (footprint "eagle-import:SJ_RND2")
      (libsource (lib "eagle-import") (part "SJRND2"))
    )
    (comp (ref "SJ14")
      (value "SJRND2")
      (footprint "eagle-import:SJ_RND2")
      (libsource (lib "eagle-import") (part "SJRND2"))
    )
    (comp (ref "SJ15")
      (value "SJ-C")
      (footprint "eagle-import:SJW-C")
      (libsource (lib "eagle-import") (part "SJ-C"))
    )
    (comp (ref "SJ16")
      (value "SJRND2")
      (footprint "eagle-import:SJ_RND2")
      (libsource (lib "eagle-import") (part "SJRND2"))
    )
    (comp (ref "SJ17")
      (value "SJRND2")
      (footprint "eagle-import:SJ_RND2")
      (libsource (lib "eagle-import") (part "SJRND2"))
    )
    (comp (ref "SJ18")
      (value "SJRND2")
      (footprint "eagle-import:SJ_RND2")
      (libsource (lib "eagle-import") (part "SJRND2"))
    )
    (comp (ref "SJ19")
      (value "SJRND2")
      (footprint "eagle-import:SJ_RND2")
      (libsource (lib "eagle-import") (part "SJRND2"))
    )
    (comp (ref "U$1")
      (value "NUCLEO_64_GENERIC")
      (footprint "eagle-import:NUCLEO_BRD_BASE64")
      (libsource (lib "eagle-import") (part "NUCLEO_64_GENERIC"))
    )
    (comp (ref "U1")
      (value "74HC166")
      (footprint "eagle-import:DIL16")
      (libsource (lib "eagle-import") (part "74166N"))
    )
    (comp (ref "U2")
      (value "74HC166")
      (footprint "eagle-import:DIL16")
      (libsource (lib "eagle-import") (part "74166N"))
    )
    (comp (ref "U3")
      (value "TC4426/28")
      (footprint "eagle-import:DIL08-LONG")
      (libsource (lib "eagle-import") (part "TC4426APDIP"))
    )
    (comp (ref "U4")
      (value "TC4426/28")
      (footprint "eagle-import:DIL08-LONG")
      (libsource (lib "eagle-import") (part "TC4426APDIP"))
    )
    (comp (ref "U5")
      (value "TC4426/28")
      (footprint "eagle-import:DIL08-LONG")
      (libsource (lib "eagle-import") (part "TC4426APDIP"))
    )
    (comp (ref "U6")
      (value "TC4426/28")
      (footprint "eagle-import:DIL08-LONG")
      (libsource (lib "eagle-import") (part "TC4426APDIP"))
    )
    (comp (ref "U7")
      (value "CAN-TXR-PDIP")
      (footprint "eagle-import:DIL08")
      (libsource (lib "eagle-import") (part "PCA82C250"))
    )
    (comp (ref "U7B")
      (value "CAN-TXR-SO8")
      (footprint "eagle-import:SO-08")
      (libsource (lib "eagle-import") (part "MCP2551-SN"))
    )
    (comp (ref "U8")
      (value "AP1509-50")
      (footprint "eagle-import:SO-08")
      (libsource (lib "eagle-import") (part "AP1509"))
    )
    (comp (ref "U8B")
      (value "LM2574N-5.0")
      (footprint "eagle-import:DIL08")
      (libsource (lib "eagle-import") (part "LM2574?-N5.0"))
    )
    (comp (ref "U9")
      (value "LM324N")
      (footprint "eagle-import:DIL14")
      (libsource (lib "eagle-import") (part "LM324N"))
    )
    (comp (ref "U10")
      (value "LM324N")
      (footprint "eagle-import:DIL14")
      (libsource (lib "eagle-import") (part "LM324N"))
    )
    (comp (ref "U11")
      (value "74AHCT595N")
      (footprint "eagle-import:DIL16")
      (libsource (lib "eagle-import") (part "74595NHCT"))
    )
    (comp (ref "U12")
      (value "ULN2803A")
      (footprint "eagle-import:DIL18-THIN")
      (libsource (lib "eagle-import") (part "ULN2803A"))
    )
    (comp (ref "U13")
      (value "74AHCT595N")
      (footprint "eagle-import:DIL16")
      (libsource (lib "eagle-import") (part "74595NHCT"))
    )
    (comp (ref "U14")
      (value "ULN2803A")
      (footprint "eagle-import:DIL18-THIN")
      (libsource (lib "eagle-import") (part "ULN2803A"))
    )
    (comp (ref "X1")
      (value "M08-SCREW")
      (footprint "eagle-import:1X08_TERMINAL")
      (libsource (lib "eagle-import") (part "M08-SCREW"))
    )
    (comp (ref "X2")
      (value "M08-SCREW")
      (footprint "eagle-import:1X08_TERMINAL")
      (libsource (lib "eagle-import") (part "M08-SCREW"))
    )
    (comp (ref "X3")
      (value "M08-SCREW")
      (footprint "eagle-import:1X08_TERMINAL")
      (libsource (lib "eagle-import") (part "M08-SCREW"))
    )
    (comp (ref "X4")
      (value "PORTD")
      (footprint "eagle-import:1X08_TERMINAL")
      (libsource (lib "eagle-import") (part "M08-SCREW"))
    )
    (comp (ref "X5")
      (value "PORTE")
      (footprint "eagle-import:1X08_TERMINAL")
      (libsource (lib "eagle-import") (part "M08-SCREW"))
    )
    (comp (ref "X6")
      (value "CONNECTOR-M023.5MM-LOCK")
      (footprint "eagle-import:SCREWTERMINAL-3.5MM-2_LOCK")
      (libsource (lib "eagle-import") (part "CONNECTOR-M023.5MM-LOCK"))
    )
  )
  (nets
    (net (code "1") (name "+3V3") (class "Default")
      (node (ref "C11") (pin "1") (pinfunction "1_1") (pintype "passive"))
      (node (ref "C4") (pin "1") (pinfunction "1_1") (pintype "passive"))
      (node (ref "R1") (pin "2") (pinfunction "2_2") (pintype "passive"))
      (node (ref "R45") (pin "1") (pinfunction "1_1") (pintype "passive"))
      (node (ref "R46") (pin "1") (pinfunction "1_1") (pintype "passive"))
      (node (ref "R47") (pin "1") (pinfunction "1_1") (pintype "passive"))
      (node (ref "R48") (pin "1") (pinfunction "1_1") (pintype "passive"))
      (node (ref "R49") (pin "1") (pinfunction "1_1") (pintype "passive"))
      (node (ref "R50") (pin "1") (pinfunction "1_1") (pintype "passive"))
      (node (ref "R51") (pin "1") (pinfunction "1_1") (pintype "passive"))
      (node (ref "R52") (pin "1") (pinfunction "1_1") (pintype "passive"))
      (node (ref "R53") (pin "1") (pinfunction "1_1") (pintype "passive"))
      (node (ref "R54") (pin "1") (pinfunction "1_1") (pintype "passive"))
      (node (ref "R55") (pin "1") (pinfunction "1_1") (pintype "passive"))
      (node (ref "R56") (pin "1") (pinfunction "1_1") (pintype "passive"))
      (node (ref "R57") (pin "1") (pinfunction "1_1") (pintype "passive"))
      (node (ref "R58") (pin "1") (pinfunction "1_1") (pintype "passive"))
      (node (ref "R59") (pin "1") (pinfunction "1_1") (pintype "passive"))
      (node (ref "R60") (pin "1") (pinfunction "1_1") (pintype "passive"))
      (node (ref "RN2") (pin "1") (pinfunction "1_1") (pintype "passive"))
      (node (ref "RN4") (pin "1") (pinfunction "1_1") (pintype "passive"))
      (node (ref "SJ18") (pin "P$1") (pinfunction "1_P$1") (pintype "passive"))
      (node (ref "U$1") (pin "3V3") (pinfunction "3V3_3V3") (pintype "power_in"))
      (node (ref "U1") (pin "1") (pinfunction "SER_1") (pintype "input"))
      (node (ref "U1") (pin "16") (pinfunction "VCC_16") (pintype "power_in"))
      (node (ref "U1") (pin "9") (pinfunction "CLR_9") (pintype "input"))
      (node (ref "U2") (pin "16") (pinfunction "VCC_16") (pintype "power_in"))
      (node (ref "U2") (pin "9") (pinfunction "CLR_9") (pintype "input"))
    )
    (net (code "2") (name "+5V") (class "Default")
      (node (ref "C3") (pin "1") (pinfunction "1_1") (pintype "passive"))
      (node (ref "C5") (pin "1") (pinfunction "1_1") (pintype "passive"))
      (node (ref "C8") (pin "1") (pinfunction "1_1") (pintype "passive"))
      (node (ref "C9") (pin "1") (pinfunction "1_1") (pintype "passive"))
      (node (ref "JP1") (pin "3") (pinfunction "3_3") (pintype "passive"))
      (node (ref "JP2") (pin "6") (pinfunction "6_6") (pintype "passive"))
      (node (ref "JP5") (pin "3") (pinfunction "3_3") (pintype "passive"))
      (node (ref "JP5") (pin "4") (pinfunction "4_4") (pintype "passive"))
      (node (ref "JP6") (pin "3") (pinfunction "3_3") (pintype "passive"))
      (node (ref "JP6") (pin "4") (pinfunction "4_4") (pintype "passive"))
      (node (ref "JP7") (pin "3") (pinfunction "3_3") (pintype "passive"))
      (node (ref "JP7") (pin "4") (pinfunction "4_4") (pintype "passive"))
      (node (ref "JP8") (pin "3") (pinfunction "3_3") (pintype "passive"))
      (node (ref "JP8") (pin "4") (pinfunction "4_4") (pintype "passive"))
      (node (ref "PORTA") (pin "6") (pinfunction "6_6") (pintype "passive"))
      (node (ref "PORTB") (pin "6") (pinfunction "6_6") (pintype "passive"))
      (node (ref "PORTC") (pin "6") (pinfunction "6_6") (pintype "passive"))
      (node (ref "R19") (pin "2") (pinfunction "2_2") (pintype "passive"))
      (node (ref "R20") (pin "2") (pinfunction "2_2") (pintype "passive"))
      (node (ref "R21") (pin "2") (pinfunction "2_2") (pintype "passive"))
      (node (ref "R22") (pin "1") (pinfunction "1_1") (pintype "passive"))
      (node (ref "R23") (pin "1") (pinfunction "1_1") (pintype "passive"))
      (node (ref "R24") (pin "1") (pinfunction "1_1") (pintype "passive"))
      (node (ref "R25") (pin "1") (pinfunction "1_1") (pintype "passive"))
      (node (ref "R26") (pin "1") (pinfunction "1_1") (pintype "passive"))
      (node (ref "R27") (pin "1") (pinfunction "1_1") (pintype "passive"))
      (node (ref "R62") (pin "1") (pinfunction "1_1") (pintype "passive"))
      (node (ref "R63") (pin "1") (pinfunction "1_1") (pintype "passive"))
      (node (ref "R64") (pin "1") (pinfunction "1_1") (pintype "passive"))
      (node (ref "R65") (pin "1") (pinfunction "1_1") (pintype "passive"))
      (node (ref "R66") (pin "1") (pinfunction "1_1") (pintype "passive"))
      (node (ref "R67") (pin "1") (pinfunction "1_1") (pintype "passive"))
      (node (ref "SJ1") (pin "P$2") (pinfunction "2_P$2") (pintype "passive"))
      (node (ref "SJ10") (pin "P$2") (pinfunction "2_P$2") (pintype "passive"))
      (node (ref "SJ4") (pin "P$2") (pinfunction "2_P$2") (pintype "passive"))
      (node (ref "SJ7") (pin "P$2") (pinfunction "2_P$2") (pintype "passive"))
      (node (ref "U$1") (pin "5V2") (pinfunction "5V2_5V2") (pintype "power_in"))
      (node (ref "U11") (pin "10") (pinfunction "SCL_10") (pintype "input"))
      (node (ref "U11") (pin "16") (pinfunction "VCC_16") (pintype "power_in"))
      (node (ref "U13") (pin "10") (pinfunction "SCL_10") (pintype "input"))
      (node (ref "U13") (pin "16") (pinfunction "VCC_16") (pintype "power_in"))
      (node (ref "U7") (pin "3") (pinfunction "VCC_3") (pintype "power_in"))
      (node (ref "U7B") (pin "3") (pinfunction "VDD_3") (pintype "power_in"))
      (node (ref "X6") (pin "1") (pinfunction "1_1") (pintype "passive"))
    )
    (net (code "3") (name "+12V") (class "Default")
      (node (ref "C10") (pin "1") (pinfunction "1_1") (pintype "passive"))
      (node (ref "C6") (pin "1") (pinfunction "1_1") (pintype "passive"))
      (node (ref "C7") (pin "1") (pinfunction "1_1") (pintype "passive"))
      (node (ref "J3") (pin "1") (pinfunction "1_1") (pintype "passive"))
      (node (ref "JP2") (pin "7") (pinfunction "7_7") (pintype "passive"))
      (node (ref "JP4") (pin "2") (pinfunction "2_2") (pintype "passive"))
      (node (ref "SJ11") (pin "P$2") (pinfunction "2_P$2") (pintype "passive"))
      (node (ref "SJ14") (pin "P$2") (pinfunction "2_P$2") (pintype "passive"))
      (node (ref "SJ2") (pin "P$2") (pinfunction "2_P$2") (pintype "passive"))
      (node (ref "SJ5") (pin "P$2") (pinfunction "2_P$2") (pintype "passive"))
      (node (ref "SJ8") (pin "P$2") (pinfunction "2_P$2") (pintype "passive"))
      (node (ref "U10") (pin "4") (pinfunction "V+_4") (pintype "power_in"))
      (node (ref "U3") (pin "6") (pinfunction "VDD_6") (pintype "power_in"))
      (node (ref "U4") (pin "6") (pinfunction "VDD_6") (pintype "power_in"))
      (node (ref "U5") (pin "6") (pinfunction "VDD_6") (pintype "power_in"))
      (node (ref "U6") (pin "6") (pinfunction "VDD_6") (pintype "power_in"))
      (node (ref "U8") (pin "1") (pinfunction "VIN_1") (pintype "bidirectional"))
      (node (ref "U8B") (pin "5") (pinfunction "IN_5") (pintype "input"))
      (node (ref "U9") (pin "4") (pinfunction "V+_4") (pintype "power_in"))
    )
    (net (code "4") (name "/AGND") (class "Default")
      (node (ref "U$1") (pin "AGND") (pinfunction "AGND_AGND") (pintype "power_in"))
    )
    (net (code "5") (name "/AVDD") (class "Default")
      (node (ref "U$1") (pin "AVDD") (pinfunction "AVDD_AVDD") (pintype "power_in"))
    )
    (net (code "6") (name "/CANH") (class "Default")
      (node (ref "J1") (pin "1") (pinfunction "1_1") (pintype "passive"))
      (node (ref "J2") (pin "1") (pinfunction "1_1") (pintype "passive"))
      (node (ref "U7") (pin "7") (pinfunction "CANH_7") (pintype "bidirectional"))
      (node (ref "U7B") (pin "7") (pinfunction "CANH_7") (pintype "bidirectional"))
    )
    (net (code "7") (name "/CANL") (class "Default")
      (node (ref "J1") (pin "2") (pinfunction "2_2") (pintype "passive"))
      (node (ref "J2") (pin "2") (pinfunction "2_2") (pintype "passive"))
      (node (ref "U7") (pin "6") (pinfunction "CANL_6") (pintype "bidirectional"))
      (node (ref "U7B") (pin "6") (pinfunction "CANL_6") (pintype "bidirectional"))
    )
    (net (code "8") (name "/GND4") (class "Default")
      (node (ref "U$1") (pin "GND4") (pinfunction "GND4_GND4") (pintype "power_in"))
    )
    (net (code "9") (name "/PWR_POS") (class "Default")
      (node (ref "J1") (pin "8") (pinfunction "8_8") (pintype "passive"))
      (node (ref "J2") (pin "8") (pinfunction "8_8") (pintype "passive"))
      (node (ref "R40") (pin "2") (pinfunction "2_2") (pintype "passive"))
    )
    (net (code "10") (name "/U5V") (class "Default")
      (node (ref "U$1") (pin "U5V") (pinfunction "U5V_U5V") (pintype "power_in"))
    )
    (net (code "11") (name "/VBAT") (class "Default")
      (node (ref "U$1") (pin "VBAT") (pinfunction "VBAT_VBAT") (pintype "power_in"))
    )
    (net (code "12") (name "/VDD") (class "Default")
      (node (ref "U$1") (pin "VDD") (pinfunction "VDD_VDD") (pintype "power_in"))
    )
    (net (code "13") (name "CANRX") (class "Default")
      (node (ref "U$1") (pin "PB8") (pinfunction "PB8_PB8") (pintype "bidirectional"))
      (node (ref "U7") (pin "4") (pinfunction "RXD_4") (pintype "output"))
      (node (ref "U7B") (pin "4") (pinfunction "RXD_4") (pintype "bidirectional"))
    )
    (net (code "14") (name "CANTX") (class "Default")
      (node (ref "U$1") (pin "PB9") (pinfunction "PB9_PB9") (pintype "bidirectional"))
      (node (ref "U7") (pin "1") (pinfunction "TXD_1") (pintype "input"))
      (node (ref "U7B") (pin "1") (pinfunction "TXD_1") (pintype "bidirectional"))
    )
    (net (code "15") (name "E_CS") (class "Default")
      (node (ref "JP2") (pin "4") (pinfunction "4_4") (pintype "passive"))
      (node (ref "R23") (pin "2") (pinfunction "2_2") (pintype "passive"))
      (node (ref "U$1") (pin "PC10") (pinfunction "PC10_PC10") (pintype "bidirectional"))
    )
    (net (code "16") (name "E_LAT") (class "Default")
      (node (ref "JP2") (pin "5") (pinfunction "5_5") (pintype "passive"))
      (node (ref "R22") (pin "2") (pinfunction "2_2") (pintype "passive"))
      (node (ref "U$1") (pin "PC11") (pinfunction "PC11_PC11") (pintype "bidirectional"))
    )
    (net (code "17") (name "GND") (class "Default")
      (node (ref "C1") (pin "2") (pinfunction "2_2") (pintype "passive"))
      (node (ref "C10") (pin "2") (pinfunction "2_2") (pintype "passive"))
      (node (ref "C11") (pin "2") (pinfunction "2_2") (pintype "passive"))
      (node (ref "C2") (pin "-") (pinfunction "-_-") (pintype "passive"))
      (node (ref "C3") (pin "2") (pinfunction "2_2") (pintype "passive"))
      (node (ref "C4") (pin "2") (pinfunction "2_2") (pintype "passive"))
      (node (ref "C5") (pin "2") (pinfunction "2_2") (pintype "passive"))
      (node (ref "C6") (pin "2") (pinfunction "2_2") (pintype "passive"))
      (node (ref "C7") (pin "2") (pinfunction "2_2") (pintype "passive"))
      (node (ref "C8") (pin "2") (pinfunction "2_2") (pintype "passive"))
      (node (ref "C9") (pin "2") (pinfunction "2_2") (pintype "passive"))
      (node (ref "D1") (pin "A") (pinfunction "A_A") (pintype "passive"))
      (node (ref "D3") (pin "A") (pinfunction "A_A") (pintype "passive"))
      (node (ref "J1") (pin "3") (pinfunction "3_3") (pintype "passive"))
      (node (ref "J1") (pin "6") (pinfunction "6_6") (pintype "passive"))
      (node (ref "J1") (pin "7") (pinfunction "7_7") (pintype "passive"))
      (node (ref "J2") (pin "3") (pinfunction "3_3") (pintype "passive"))
      (node (ref "J2") (pin "6") (pinfunction "6_6") (pintype "passive"))
      (node (ref "J2") (pin "7") (pinfunction "7_7") (pintype "passive"))
      (node (ref "J3") (pin "2") (pinfunction "2_2") (pintype "passive"))
      (node (ref "J3") (pin "3") (pinfunction "3_3") (pintype "passive"))
      (node (ref "JP1") (pin "4") (pinfunction "4_4") (pintype "passive"))
      (node (ref "JP2") (pin "8") (pinfunction "8_8") (pintype "passive"))
      (node (ref "JP5") (pin "5") (pinfunction "5_5") (pintype "passive"))
      (node (ref "JP5") (pin "6") (pinfunction "6_6") (pintype "passive"))
      (node (ref "JP6") (pin "5") (pinfunction "5_5") (pintype "passive"))
      (node (ref "JP6") (pin "6") (pinfunction "6_6") (pintype "passive"))
      (node (ref "JP7") (pin "5") (pinfunction "5_5") (pintype "passive"))
      (node (ref "JP7") (pin "6") (pinfunction "6_6") (pintype "passive"))
      (node (ref "JP8") (pin "5") (pinfunction "5_5") (pintype "passive"))
      (node (ref "JP8") (pin "6") (pinfunction "6_6") (pintype "passive"))
      (node (ref "PORTA") (pin "5") (pinfunction "5_5") (pintype "passive"))
      (node (ref "PORTB") (pin "5") (pinfunction "5_5") (pintype "passive"))
      (node (ref "PORTC") (pin "5") (pinfunction "5_5") (pintype "passive"))
      (node (ref "Q1") (pin "2") (pinfunction "S_2") (pintype "passive"))
      (node (ref "Q10") (pin "2") (pinfunction "S_2") (pintype "passive"))
      (node (ref "Q11") (pin "2") (pinfunction "S_2") (pintype "passive"))
      (node (ref "Q12") (pin "2") (pinfunction "S_2") (pintype "passive"))
      (node (ref "Q13") (pin "2") (pinfunction "S_2") (pintype "passive"))
      (node (ref "Q14") (pin "2") (pinfunction "S_2") (pintype "passive"))
      (node (ref "Q15") (pin "2") (pinfunction "S_2") (pintype "passive"))
      (node (ref "Q16") (pin "2") (pinfunction "S_2") (pintype "passive"))
      (node (ref "Q2") (pin "2") (pinfunction "S_2") (pintype "passive"))
      (node (ref "Q3") (pin "2") (pinfunction "S_2") (pintype "passive"))
      (node (ref "Q4") (pin "2") (pinfunction "S_2") (pintype "passive"))
      (node (ref "Q5") (pin "2") (pinfunction "S_2") (pintype "passive"))
      (node (ref "Q6") (pin "2") (pinfunction "S_2") (pintype "passive"))
      (node (ref "Q7") (pin "2") (pinfunction "S_2") (pintype "passive"))
      (node (ref "Q8") (pin "2") (pinfunction "S_2") (pintype "passive"))
      (node (ref "Q9") (pin "2") (pinfunction "S_2") (pintype "passive"))
      (node (ref "R2") (pin "1") (pinfunction "1_1") (pintype "passive"))
      (node (ref "R61") (pin "2") (pinfunction "2_2") (pintype "passive"))
      (node (ref "SJ12") (pin "P$2") (pinfunction "2_P$2") (pintype "passive"))
      (node (ref "SJ3") (pin "2") (pinfunction "2_2") (pintype "passive"))
      (node (ref "SJ6") (pin "P$2") (pinfunction "2_P$2") (pintype "passive"))
      (node (ref "SJ9") (pin "2") (pinfunction "2_2") (pintype "passive"))
      (node (ref "U$1") (pin "GND3") (pinfunction "GND3_GND3") (pintype "power_in"))
      (node (ref "U$1") (pin "GND5") (pinfunction "GND5_GND5") (pintype "power_in"))
      (node (ref "U$1") (pin "GND6") (pinfunction "GND6_GND6") (pintype "power_in"))
      (node (ref "U$1") (pin "GND7") (pinfunction "GND7_GND7") (pintype "power_in"))
      (node (ref "U$1") (pin "GND8") (pinfunction "GND8_GND8") (pintype "power_in"))
      (node (ref "U1") (pin "6") (pinfunction "INH_6") (pintype "input"))
      (node (ref "U1") (pin "8") (pinfunction "GND_8") (pintype "power_in"))
      (node (ref "U10") (pin "11") (pinfunction "V-_11") (pintype "power_in"))
      (node (ref "U11") (pin "13") (pinfunction "G_13") (pintype "input"))
      (node (ref "U11") (pin "8") (pinfunction "GND_8") (pintype "power_in"))
      (node (ref "U13") (pin "13") (pinfunction "G_13") (pintype "input"))
      (node (ref "U13") (pin "8") (pinfunction "GND_8") (pintype "power_in"))
      (node (ref "U2") (pin "6") (pinfunction "INH_6") (pintype "input"))
      (node (ref "U2") (pin "8") (pinfunction "GND_8") (pintype "power_in"))
      (node (ref "U3") (pin "3") (pinfunction "VSS_3") (pintype "power_in"))
      (node (ref "U4") (pin "3") (pinfunction "VSS_3") (pintype "power_in"))
      (node (ref "U5") (pin "3") (pinfunction "VSS_3") (pintype "power_in"))
      (node (ref "U6") (pin "3") (pinfunction "VSS_3") (pintype "power_in"))
      (node (ref "U7") (pin "2") (pinfunction "GND_2") (pintype "power_in"))
      (node (ref "U7B") (pin "2") (pinfunction "VSS_2") (pintype "power_in"))
      (node (ref "U8") (pin "4") (pinfunction "SD_4") (pintype "bidirectional"))
      (node (ref "U8") (pin "5") (pinfunction "GND1_5") (pintype "power_in"))
      (node (ref "U8") (pin "6") (pinfunction "GND2_6") (pintype "power_in"))
      (node (ref "U8") (pin "7") (pinfunction "GND3_7") (pintype "power_in"))
      (node (ref "U8") (pin "8") (pinfunction "GND4_8") (pintype "power_in"))
      (node (ref "U8B") (pin "2") (pinfunction "GNDSIG_2") (pintype "input"))
      (node (ref "U8B") (pin "3") (pinfunction "~{ON/OFF}_3") (pintype "input"))
      (node (ref "U8B") (pin "4") (pinfunction "GND_4") (pintype "power_in"))
      (node (ref "U9") (pin "11") (pinfunction "V-_11") (pintype "power_in"))
      (node (ref "X6") (pin "2") (pinfunction "2_2") (pintype "passive"))
    )
    (net (code "18") (name "I2CSCL") (class "Default")
      (node (ref "JP1") (pin "1") (pinfunction "1_1") (pintype "passive"))
      (node (ref "R62") (pin "2") (pinfunction "2_2") (pintype "passive"))
      (node (ref "U$1") (pin "PB6") (pinfunction "PB6_PB6") (pintype "bidirectional"))
    )
    (net (code "19") (name "I2CSDA") (class "Default")
      (node (ref "JP1") (pin "2") (pinfunction "2_2") (pintype "passive"))
      (node (ref "R63") (pin "2") (pinfunction "2_2") (pintype "passive"))
      (node (ref "U$1") (pin "PB7") (pinfunction "PB7_PB7") (pintype "bidirectional"))
    )
    (net (code "20") (name "ILAT") (class "Default")
      (node (ref "U$1") (pin "PA6") (pinfunction "PA6_PA6") (pintype "bidirectional"))
      (node (ref "U1") (pin "15") (pinfunction "SH/~{LD}_15") (pintype "input"))
      (node (ref "U2") (pin "15") (pinfunction "SH/~{LD}_15") (pintype "input"))
    )
    (net (code "21") (name "MISO") (class "Default")
      (node (ref "JP2") (pin "1") (pinfunction "1_1") (pintype "passive"))
      (node (ref "U$1") (pin "PB4") (pinfunction "PB4_PB4") (pintype "bidirectional"))
    )
    (net (code "22") (name "MISO2") (class "Default")
      (node (ref "SJ13") (pin "P$2") (pinfunction "2_P$2") (pintype "passive"))
      (node (ref "SJ19") (pin "P$2") (pinfunction "2_P$2") (pintype "passive"))
      (node (ref "U$1") (pin "PC2") (pinfunction "PC2_PC2") (pintype "bidirectional"))
      (node (ref "U2") (pin "13") (pinfunction "QH_13") (pintype "output"))
    )
    (net (code "23") (name "MOSI") (class "Default")
      (node (ref "R20") (pin "1") (pinfunction "1_1") (pintype "passive"))
      (node (ref "SJ15") (pin "1") (pinfunction "1_1") (pintype "passive"))
      (node (ref "SJ17") (pin "P$2") (pinfunction "2_P$2") (pintype "passive"))
      (node (ref "U$1") (pin "PB5") (pinfunction "PB5_PB5") (pintype "bidirectional"))
      (node (ref "U11") (pin "14") (pinfunction "SER_14") (pintype "input"))
    )
    (net (code "24") (name "Net-(D2-PadA)") (class "Default")
      (node (ref "D2") (pin "A") (pinfunction "A_A") (pintype "passive"))
      (node (ref "D4") (pin "A") (pinfunction "A_A") (pintype "passive"))
      (node (ref "JP4") (pin "4") (pinfunction "4_4") (pintype "passive"))
    )
    (net (code "25") (name "Net-(D2-PadC)") (class "Default")
      (node (ref "D2") (pin "C") (pinfunction "C_C") (pintype "passive"))
      (node (ref "D4") (pin "C") (pinfunction "C_C") (pintype "passive"))
      (node (ref "JP4") (pin "1") (pinfunction "1_1") (pintype "passive"))
    )
    (net (code "26") (name "Net-(J1-Pad4)") (class "Default")
      (node (ref "J1") (pin "4") (pinfunction "4_4") (pintype "passive"))
      (node (ref "J2") (pin "4") (pinfunction "4_4") (pintype "passive"))
    )
    (net (code "27") (name "Net-(J1-Pad5)") (class "Default")
      (node (ref "J1") (pin "5") (pinfunction "5_5") (pintype "passive"))
      (node (ref "J2") (pin "5") (pinfunction "5_5") (pintype "passive"))
    )
    (net (code "28") (name "Net-(JP4-Pad3)") (class "Default")
      (node (ref "JP4") (pin "3") (pinfunction "3_3") (pintype "passive"))
      (node (ref "R40") (pin "1") (pinfunction "1_1") (pintype "passive"))
    )
    (net (code "29") (name "Net-(PORTA-Pad1)") (class "Default")
      (node (ref "PORTA") (pin "1") (pinfunction "1_1") (pintype "passive"))
      (node (ref "R44") (pin "2") (pinfunction "2_2") (pintype "passive"))
      (node (ref "R53") (pin "2") (pinfunction "2_2") (pintype "passive"))
      (node (ref "RN3") (pin "1") (pinfunction "1_1") (pintype "passive"))
      (node (ref "RN4") (pin "9") (pinfunction "9_9") (pintype "passive"))
      (node (ref "X1") (pin "1") (pinfunction "1_1") (pintype "passive"))
    )
    (net (code "30") (name "Net-(PORTB-Pad1)") (class "Default")
      (node (ref "PORTB") (pin "1") (pinfunction "1_1") (pintype "passive"))
      (node (ref "R35") (pin "2") (pinfunction "2_2") (pintype "passive"))
      (node (ref "R45") (pin "2") (pinfunction "2_2") (pintype "passive"))
      (node (ref "RN1") (pin "1") (pinfunction "1_1") (pintype "passive"))
      (node (ref "RN2") (pin "9") (pinfunction "9_9") (pintype "passive"))
      (node (ref "X2") (pin "1") (pinfunction "1_1") (pintype "passive"))
    )
    (net (code "31") (name "Net-(Q1-D)") (class "Default")
      (node (ref "Q1") (pin "3") (pinfunction "D_3") (pintype "passive"))
      (node (ref "U12") (pin "18") (pinfunction "O1_18") (pintype "open_collector"))
      (node (ref "X5") (pin "1") (pinfunction "1_1") (pintype "passive"))
    )
    (net (code "32") (name "Net-(Q1-G)") (class "Default")
      (node (ref "Q1") (pin "1") (pinfunction "G_1") (pintype "passive"))
      (node (ref "R3") (pin "2") (pinfunction "2_2") (pintype "passive"))
    )
    (net (code "33") (name "Net-(Q2-D)") (class "Default")
      (node (ref "Q2") (pin "3") (pinfunction "D_3") (pintype "passive"))
      (node (ref "U12") (pin "17") (pinfunction "O2_17") (pintype "open_collector"))
      (node (ref "X5") (pin "2") (pinfunction "2_2") (pintype "passive"))
    )
    (net (code "34") (name "Net-(Q2-G)") (class "Default")
      (node (ref "Q2") (pin "1") (pinfunction "G_1") (pintype "passive"))
      (node (ref "R4") (pin "2") (pinfunction "2_2") (pintype "passive"))
    )
    (net (code "35") (name "Net-(Q3-D)") (class "Default")
      (node (ref "Q3") (pin "3") (pinfunction "D_3") (pintype "passive"))
      (node (ref "U12") (pin "16") (pinfunction "O3_16") (pintype "open_collector"))
      (node (ref "X5") (pin "3") (pinfunction "3_3") (pintype "passive"))
    )
    (net (code "36") (name "Net-(Q3-G)") (class "Default")
      (node (ref "Q3") (pin "1") (pinfunction "G_1") (pintype "passive"))
      (node (ref "R5") (pin "2") (pinfunction "2_2") (pintype "passive"))
    )
    (net (code "37") (name "Net-(Q4-D)") (class "Default")
      (node (ref "Q4") (pin "3") (pinfunction "D_3") (pintype "passive"))
      (node (ref "U12") (pin "15") (pinfunction "O4_15") (pintype "open_collector"))
      (node (ref "X5") (pin "4") (pinfunction "4_4") (pintype "passive"))
    )
    (net (code "38") (name "Net-(Q4-G)") (class "Default")
      (node (ref "Q4") (pin "1") (pinfunction "G_1") (pintype "passive"))
      (node (ref "R6") (pin "2") (pinfunction "2_2") (pintype "passive"))
    )
    (net (code "39") (name "Net-(Q5-D)") (class "Default")
      (node (ref "Q5") (pin "3") (pinfunction "D_3") (pintype "passive"))
      (node (ref "U12") (pin "14") (pinfunction "O5_14") (pintype "open_collector"))
      (node (ref "X5") (pin "5") (pinfunction "5_5") (pintype "passive"))
    )
    (net (code "40") (name "Net-(Q5-G)") (class "Default")
      (node (ref "Q5") (pin "1") (pinfunction "G_1") (pintype "passive"))
      (node (ref "R7") (pin "2") (pinfunction "2_2") (pintype "passive"))
    )
    (net (code "41") (name "Net-(Q6-D)") (class "Default")
      (node (ref "Q6") (pin "3") (pinfunction "D_3") (pintype "passive"))
      (node (ref "U12") (pin "13") (pinfunction "O6_13") (pintype "open_collector"))
      (node (ref "X5") (pin "6") (pinfunction "6_6") (pintype "passive"))
    )
    (net (code "42") (name "Net-(Q6-G)") (class "Default")
      (node (ref "Q6") (pin "1") (pinfunction "G_1") (pintype "passive"))
      (node (ref "R8") (pin "2") (pinfunction "2_2") (pintype "passive"))
    )
    (net (code "43") (name "Net-(Q7-D)") (class "Default")
      (node (ref "Q7") (pin "3") (pinfunction "D_3") (pintype "passive"))
      (node (ref "U12") (pin "12") (pinfunction "O7_12") (pintype "open_collector"))
      (node (ref "X5") (pin "7") (pinfunction "7_7") (pintype "passive"))
    )
    (net (code "44") (name "Net-(Q7-G)") (class "Default")
      (node (ref "Q7") (pin "1") (pinfunction "G_1") (pintype "passive"))
      (node (ref "R9") (pin "2") (pinfunction "2_2") (pintype "passive"))
    )
    (net (code "45") (name "Net-(Q8-D)") (class "Default")
      (node (ref "Q8") (pin "3") (pinfunction "D_3") (pintype "passive"))
      (node (ref "U12") (pin "11") (pinfunction "O8_11") (pintype "open_collector"))
      (node (ref "X5") (pin "8") (pinfunction "8_8") (pintype "passive"))
    )
    (net (code "46") (name "Net-(Q8-G)") (class "Default")
      (node (ref "Q8") (pin "1") (pinfunction "G_1") (pintype "passive"))
      (node (ref "R10") (pin "2") (pinfunction "2_2") (pintype "passive"))
    )
    (net (code "47") (name "Net-(Q9-D)") (class "Default")
      (node (ref "Q9") (pin "3") (pinfunction "D_3") (pintype "passive"))
      (node (ref "U14") (pin "18") (pinfunction "O1_18") (pintype "open_collector"))
      (node (ref "X4") (pin "1") (pinfunction "1_1") (pintype "passive"))
    )
    (net (code "48") (name "Net-(Q9-G)") (class "Default")
      (node (ref "Q9") (pin "1") (pinfunction "G_1") (pintype "passive"))
      (node (ref "R11") (pin "2") (pinfunction "2_2") (pintype "passive"))
    )
    (net (code "49") (name "Net-(Q10-D)") (class "Default")
      (node (ref "Q10") (pin "3") (pinfunction "D_3") (pintype "passive"))
      (node (ref "U14") (pin "17") (pinfunction "O2_17") (pintype "open_collector"))
      (node (ref "X4") (pin "2") (pinfunction "2_2") (pintype "passive"))
    )
    (net (code "50") (name "Net-(Q10-G)") (class "Default")
      (node (ref "Q10") (pin "1") (pinfunction "G_1") (pintype "passive"))
      (node (ref "R12") (pin "2") (pinfunction "2_2") (pintype "passive"))
    )
    (net (code "51") (name "Net-(Q11-D)") (class "Default")
      (node (ref "Q11") (pin "3") (pinfunction "D_3") (pintype "passive"))
      (node (ref "U14") (pin "16") (pinfunction "O3_16") (pintype "open_collector"))
      (node (ref "X4") (pin "3") (pinfunction "3_3") (pintype "passive"))
    )
    (net (code "52") (name "Net-(Q11-G)") (class "Default")
      (node (ref "Q11") (pin "1") (pinfunction "G_1") (pintype "passive"))
      (node (ref "R13") (pin "2") (pinfunction "2_2") (pintype "passive"))
    )
    (net (code "53") (name "Net-(Q12-D)") (class "Default")
      (node (ref "Q12") (pin "3") (pinfunction "D_3") (pintype "passive"))
      (node (ref "U14") (pin "15") (pinfunction "O4_15") (pintype "open_collector"))
      (node (ref "X4") (pin "4") (pinfunction "4_4") (pintype "passive"))
    )
    (net (code "54") (name "Net-(Q12-G)") (class "Default")
      (node (ref "Q12") (pin "1") (pinfunction "G_1") (pintype "passive"))
      (node (ref "R14") (pin "2") (pinfunction "2_2") (pintype "passive"))
    )
    (net (code "55") (name "Net-(Q13-D)") (class "Default")
      (node (ref "Q13") (pin "3") (pinfunction "D_3") (pintype "passive"))
      (node (ref "U14") (pin "14") (pinfunction "O5_14") (pintype "open_collector"))
      (node (ref "X4") (pin "5") (pinfunction "5_5") (pintype "passive"))
    )
    (net (code "56") (name "Net-(Q13-G)") (class "Default")
      (node (ref "Q13") (pin "1") (pinfunction "G_1") (pintype "passive"))
      (node (ref "R15") (pin "2") (pinfunction "2_2") (pintype "passive"))
    )
    (net (code "57") (name "Net-(Q14-D)") (class "Default")
      (node (ref "Q14") (pin "3") (pinfunction "D_3") (pintype "passive"))
      (node (ref "U14") (pin "13") (pinfunction "O6_13") (pintype "open_collector"))
      (node (ref "X4") (pin "6") (pinfunction "6_6") (pintype "passive"))
    )
    (net (code "58") (name "Net-(Q14-G)") (class "Default")
      (node (ref "Q14") (pin "1") (pinfunction "G_1") (pintype "passive"))
      (node (ref "R16") (pin "2") (pinfunction "2_2") (pintype "passive"))
    )
    (net (code "59") (name "Net-(Q15-D)") (class "Default")
      (node (ref "Q15") (pin "3") (pinfunction "D_3") (pintype "passive"))
      (node (ref "U14") (pin "12") (pinfunction "O7_12") (pintype "open_collector"))
      (node (ref "X4") (pin "7") (pinfunction "7_7") (pintype "passive"))
    )
    (net (code "60") (name "Net-(Q15-G)") (class "Default")
      (node (ref "Q15") (pin "1") (pinfunction "G_1") (pintype "passive"))
      (node (ref "R17") (pin "2") (pinfunction "2_2") (pintype "passive"))
    )
    (net (code "61") (name "Net-(Q16-D)") (class "Default")
      (node (ref "Q16") (pin "3") (pinfunction "D_3") (pintype "passive"))
      (node (ref "U14") (pin "11") (pinfunction "O8_11") (pintype "open_collector"))
      (node (ref "X4") (pin "8") (pinfunction "8_8") (pintype "passive"))
    )
    (net (code "62") (name "Net-(Q16-G)") (class "Default")
      (node (ref "Q16") (pin "1") (pinfunction "G_1") (pintype "passive"))
      (node (ref "R18") (pin "2") (pinfunction "2_2") (pintype "passive"))
    )
    (net (code "63") (name "Net-(RN1A-2)") (class "Default")
      (node (ref "R35") (pin "1") (pinfunction "1_1") (pintype "passive"))
      (node (ref "RN1") (pin "16") (pinfunction "2_16") (pintype "passive"))
      (node (ref "U2") (pin "14") (pinfunction "H_14") (pintype "input"))
    )
    (net (code "64") (name "Net-(RN1B-1)") (class "Default")
      (node (ref "PORTB") (pin "2") (pinfunction "2_2") (pintype "passive"))
      (node (ref "R34") (pin "2") (pinfunction "2_2") (pintype "passive"))
      (node (ref "R46") (pin "2") (pinfunction "2_2") (pintype "passive"))
      (node (ref "RN1") (pin "2") (pinfunction "1_2") (pintype "passive"))
      (node (ref "RN2") (pin "8") (pinfunction "8_8") (pintype "passive"))
      (node (ref "X2") (pin "2") (pinfunction "2_2") (pintype "passive"))
    )
    (net (code "65") (name "Net-(RN1B-2)") (class "Default")
      (node (ref "R34") (pin "1") (pinfunction "1_1") (pintype "passive"))
      (node (ref "RN1") (pin "15") (pinfunction "2_15") (pintype "passive"))
      (node (ref "U2") (pin "12") (pinfunction "G_12") (pintype "input"))
    )
    (net (code "66") (name "Net-(RN1C-1)") (class "Default")
      (node (ref "PORTB") (pin "3") (pinfunction "3_3") (pintype "passive"))
      (node (ref "R33") (pin "2") (pinfunction "2_2") (pintype "passive"))
      (node (ref "R47") (pin "2") (pinfunction "2_2") (pintype "passive"))
      (node (ref "RN1") (pin "3") (pinfunction "1_3") (pintype "passive"))
      (node (ref "RN2") (pin "7") (pinfunction "7_7") (pintype "passive"))
      (node (ref "X2") (pin "3") (pinfunction "3_3") (pintype "passive"))
    )
    (net (code "67") (name "Net-(RN1C-2)") (class "Default")
      (node (ref "R33") (pin "1") (pinfunction "1_1") (pintype "passive"))
      (node (ref "RN1") (pin "14") (pinfunction "2_14") (pintype "passive"))
      (node (ref "U2") (pin "11") (pinfunction "F_11") (pintype "input"))
    )
    (net (code "68") (name "Net-(RN1D-1)") (class "Default")
      (node (ref "PORTB") (pin "4") (pinfunction "4_4") (pintype "passive"))
      (node (ref "R32") (pin "2") (pinfunction "2_2") (pintype "passive"))
      (node (ref "R48") (pin "2") (pinfunction "2_2") (pintype "passive"))
      (node (ref "RN1") (pin "4") (pinfunction "1_4") (pintype "passive"))
      (node (ref "RN2") (pin "6") (pinfunction "6_6") (pintype "passive"))
      (node (ref "X2") (pin "4") (pinfunction "4_4") (pintype "passive"))
    )
    (net (code "69") (name "Net-(RN1D-2)") (class "Default")
      (node (ref "R32") (pin "1") (pinfunction "1_1") (pintype "passive"))
      (node (ref "RN1") (pin "13") (pinfunction "2_13") (pintype "passive"))
      (node (ref "U2") (pin "10") (pinfunction "E_10") (pintype "input"))
    )
    (net (code "70") (name "Net-(RN1E-1)") (class "Default")
      (node (ref "PORTB") (pin "7") (pinfunction "7_7") (pintype "passive"))
      (node (ref "R31") (pin "2") (pinfunction "2_2") (pintype "passive"))
      (node (ref "R49") (pin "2") (pinfunction "2_2") (pintype "passive"))
      (node (ref "RN1") (pin "5") (pinfunction "1_5") (pintype "passive"))
      (node (ref "RN2") (pin "5") (pinfunction "5_5") (pintype "passive"))
      (node (ref "X2") (pin "5") (pinfunction "5_5") (pintype "passive"))
    )
    (net (code "71") (name "Net-(RN1E-2)") (class "Default")
      (node (ref "R31") (pin "1") (pinfunction "1_1") (pintype "passive"))
      (node (ref "RN1") (pin "12") (pinfunction "2_12") (pintype "passive"))
      (node (ref "U2") (pin "5") (pinfunction "D_5") (pintype "input"))
    )
    (net (code "72") (name "Net-(RN1F-1)") (class "Default")
      (node (ref "PORTB") (pin "8") (pinfunction "8_8") (pintype "passive"))
      (node (ref "R30") (pin "2") (pinfunction "2_2") (pintype "passive"))
      (node (ref "R50") (pin "2") (pinfunction "2_2") (pintype "passive"))
      (node (ref "RN1") (pin "6") (pinfunction "1_6") (pintype "passive"))
      (node (ref "RN2") (pin "4") (pinfunction "4_4") (pintype "passive"))
      (node (ref "X2") (pin "6") (pinfunction "6_6") (pintype "passive"))
    )
    (net (code "73") (name "Net-(RN1F-2)") (class "Default")
      (node (ref "R30") (pin "1") (pinfunction "1_1") (pintype "passive"))
      (node (ref "RN1") (pin "11") (pinfunction "2_11") (pintype "passive"))
      (node (ref "U2") (pin "4") (pinfunction "C_4") (pintype "input"))
    )
    (net (code "74") (name "Net-(RN1G-1)") (class "Default")
      (node (ref "PORTB") (pin "9") (pinfunction "9_9") (pintype "passive"))
      (node (ref "R29") (pin "2") (pinfunction "2_2") (pintype "passive"))
      (node (ref "R51") (pin "2") (pinfunction "2_2") (pintype "passive"))
      (node (ref "RN1") (pin "7") (pinfunction "1_7") (pintype "passive"))
      (node (ref "RN2") (pin "3") (pinfunction "3_3") (pintype "passive"))
      (node (ref "X2") (pin "7") (pinfunction "7_7") (pintype "passive"))
    )
    (net (code "75") (name "Net-(RN1G-2)") (class "Default")
      (node (ref "R29") (pin "1") (pinfunction "1_1") (pintype "passive"))
      (node (ref "RN1") (pin "10") (pinfunction "2_10") (pintype "passive"))
      (node (ref "U2") (pin "3") (pinfunction "B_3") (pintype "input"))
    )
    (net (code "76") (name "Net-(RN1H-1)") (class "Default")
      (node (ref "PORTB") (pin "10") (pinfunction "10_10") (pintype "passive"))
      (node (ref "R28") (pin "2") (pinfunction "2_2") (pintype "passive"))
      (node (ref "R52") (pin "2") (pinfunction "2_2") (pintype "passive"))
      (node (ref "RN1") (pin "8") (pinfunction "1_8") (pintype "passive"))
      (node (ref "RN2") (pin "2") (pinfunction "2_2") (pintype "passive"))
      (node (ref "X2") (pin "8") (pinfunction "8_8") (pintype "passive"))
    )
    (net (code "77") (name "Net-(RN1H-2)") (class "Default")
      (node (ref "R28") (pin "1") (pinfunction "1_1") (pintype "passive"))
      (node (ref "RN1") (pin "9") (pinfunction "2_9") (pintype "passive"))
      (node (ref "U2") (pin "2") (pinfunction "A_2") (pintype "input"))
    )
    (net (code "78") (name "Net-(RN3A-2)") (class "Default")
      (node (ref "R44") (pin "1") (pinfunction "1_1") (pintype "passive"))
      (node (ref "RN3") (pin "16") (pinfunction "2_16") (pintype "passive"))
      (node (ref "U1") (pin "14") (pinfunction "H_14") (pintype "input"))
    )
    (net (code "79") (name "Net-(RN3B-1)") (class "Default")
      (node (ref "PORTA") (pin "2") (pinfunction "2_2") (pintype "passive"))
      (node (ref "R43") (pin "2") (pinfunction "2_2") (pintype "passive"))
      (node (ref "R54") (pin "2") (pinfunction "2_2") (pintype "passive"))
      (node (ref "RN3") (pin "2") (pinfunction "1_2") (pintype "passive"))
      (node (ref "RN4") (pin "8") (pinfunction "8_8") (pintype "passive"))
      (node (ref "X1") (pin "2") (pinfunction "2_2") (pintype "passive"))
    )
    (net (code "80") (name "Net-(RN3B-2)") (class "Default")
      (node (ref "R43") (pin "1") (pinfunction "1_1") (pintype "passive"))
      (node (ref "RN3") (pin "15") (pinfunction "2_15") (pintype "passive"))
      (node (ref "U1") (pin "12") (pinfunction "G_12") (pintype "input"))
    )
    (net (code "81") (name "Net-(RN3C-1)") (class "Default")
      (node (ref "PORTA") (pin "3") (pinfunction "3_3") (pintype "passive"))
      (node (ref "R42") (pin "2") (pinfunction "2_2") (pintype "passive"))
      (node (ref "R55") (pin "2") (pinfunction "2_2") (pintype "passive"))
      (node (ref "RN3") (pin "3") (pinfunction "1_3") (pintype "passive"))
      (node (ref "RN4") (pin "7") (pinfunction "7_7") (pintype "passive"))
      (node (ref "X1") (pin "3") (pinfunction "3_3") (pintype "passive"))
    )
    (net (code "82") (name "Net-(RN3C-2)") (class "Default")
      (node (ref "R42") (pin "1") (pinfunction "1_1") (pintype "passive"))
      (node (ref "RN3") (pin "14") (pinfunction "2_14") (pintype "passive"))
      (node (ref "U1") (pin "11") (pinfunction "F_11") (pintype "input"))
    )
    (net (code "83") (name "Net-(RN3D-1)") (class "Default")
      (node (ref "PORTA") (pin "4") (pinfunction "4_4") (pintype "passive"))
      (node (ref "R41") (pin "2") (pinfunction "2_2") (pintype "passive"))
      (node (ref "R56") (pin "2") (pinfunction "2_2") (pintype "passive"))
      (node (ref "RN3") (pin "4") (pinfunction "1_4") (pintype "passive"))
      (node (ref "RN4") (pin "6") (pinfunction "6_6") (pintype "passive"))
      (node (ref "X1") (pin "4") (pinfunction "4_4") (pintype "passive"))
    )
    (net (code "84") (name "Net-(RN3D-2)") (class "Default")
      (node (ref "R41") (pin "1") (pinfunction "1_1") (pintype "passive"))
      (node (ref "RN3") (pin "13") (pinfunction "2_13") (pintype "passive"))
      (node (ref "U1") (pin "10") (pinfunction "E_10") (pintype "input"))
    )
    (net (code "85") (name "Net-(RN3E-1)") (class "Default")
      (node (ref "PORTA") (pin "7") (pinfunction "7_7") (pintype "passive"))
      (node (ref "R39") (pin "2") (pinfunction "2_2") (pintype "passive"))
      (node (ref "R57") (pin "2") (pinfunction "2_2") (pintype "passive"))
      (node (ref "RN3") (pin "5") (pinfunction "1_5") (pintype "passive"))
      (node (ref "RN4") (pin "5") (pinfunction "5_5") (pintype "passive"))
      (node (ref "X1") (pin "5") (pinfunction "5_5") (pintype "passive"))
    )
    (net (code "86") (name "Net-(RN3E-2)") (class "Default")
      (node (ref "R39") (pin "1") (pinfunction "1_1") (pintype "passive"))
      (node (ref "RN3") (pin "12") (pinfunction "2_12") (pintype "passive"))
      (node (ref "U1") (pin "5") (pinfunction "D_5") (pintype "input"))
    )
    (net (code "87") (name "Net-(RN3F-1)") (class "Default")
      (node (ref "PORTA") (pin "8") (pinfunction "8_8") (pintype "passive"))
      (node (ref "R38") (pin "2") (pinfunction "2_2") (pintype "passive"))
      (node (ref "R58") (pin "2") (pinfunction "2_2") (pintype "passive"))
      (node (ref "RN3") (pin "6") (pinfunction "1_6") (pintype "passive"))
      (node (ref "RN4") (pin "4") (pinfunction "4_4") (pintype "passive"))
      (node (ref "X1") (pin "6") (pinfunction "6_6") (pintype "passive"))
    )
    (net (code "88") (name "Net-(RN3F-2)") (class "Default")
      (node (ref "R38") (pin "1") (pinfunction "1_1") (pintype "passive"))
      (node (ref "RN3") (pin "11") (pinfunction "2_11") (pintype "passive"))
      (node (ref "U1") (pin "4") (pinfunction "C_4") (pintype "input"))
    )
    (net (code "89") (name "Net-(RN3G-1)") (class "Default")
      (node (ref "PORTA") (pin "9") (pinfunction "9_9") (pintype "passive"))
      (node (ref "R37") (pin "2") (pinfunction "2_2") (pintype "passive"))
      (node (ref "R59") (pin "2") (pinfunction "2_2") (pintype "passive"))
      (node (ref "RN3") (pin "7") (pinfunction "1_7") (pintype "passive"))
      (node (ref "RN4") (pin "3") (pinfunction "3_3") (pintype "passive"))
      (node (ref "X1") (pin "7") (pinfunction "7_7") (pintype "passive"))
    )
    (net (code "90") (name "Net-(RN3G-2)") (class "Default")
      (node (ref "R37") (pin "1") (pinfunction "1_1") (pintype "passive"))
      (node (ref "RN3") (pin "10") (pinfunction "2_10") (pintype "passive"))
      (node (ref "U1") (pin "3") (pinfunction "B_3") (pintype "input"))
    )
    (net (code "91") (name "Net-(RN3H-1)") (class "Default")
      (node (ref "PORTA") (pin "10") (pinfunction "10_10") (pintype "passive"))
      (node (ref "R36") (pin "2") (pinfunction "2_2") (pintype "passive"))
      (node (ref "R60") (pin "2") (pinfunction "2_2") (pintype "passive"))
      (node (ref "RN3") (pin "8") (pinfunction "1_8") (pintype "passive"))
      (node (ref "RN4") (pin "2") (pinfunction "2_2") (pintype "passive"))
      (node (ref "X1") (pin "8") (pinfunction "8_8") (pintype "passive"))
    )
    (net (code "92") (name "Net-(RN3H-2)") (class "Default")
      (node (ref "R36") (pin "1") (pinfunction "1_1") (pintype "passive"))
      (node (ref "RN3") (pin "9") (pinfunction "2_9") (pintype "passive"))
      (node (ref "U1") (pin "2") (pinfunction "A_2") (pintype "input"))
    )
    (net (code "93") (name "Net-(SJ1-1)") (class "Default")
      (node (ref "SJ1") (pin "P$1") (pinfunction "1_P$1") (pintype "passive"))
      (node (ref "SJ2") (pin "P$1") (pinfunction "1_P$1") (pintype "passive"))
      (node (ref "SJ3") (pin "1") (pinfunction "1_1") (pintype "passive"))
      (node (ref "U12") (pin "9") (pinfunction "GND_9") (pintype "power_in"))
    )
    (net (code "94") (name "Net-(SJ4-1)") (class "Default")
      (node (ref "SJ4") (pin "P$1") (pinfunction "1_P$1") (pintype "passive"))
      (node (ref "SJ5") (pin "P$1") (pinfunction "1_P$1") (pintype "passive"))
      (node (ref "SJ6") (pin "P$1") (pinfunction "1_P$1") (pintype "passive"))
      (node (ref "U12") (pin "10") (pinfunction "CD+_10") (pintype "passive"))
    )
    (net (code "95") (name "Net-(SJ7-1)") (class "Default")
      (node (ref "SJ7") (pin "P$1") (pinfunction "1_P$1") (pintype "passive"))
      (node (ref "SJ8") (pin "P$1") (pinfunction "1_P$1") (pintype "passive"))
      (node (ref "SJ9") (pin "1") (pinfunction "1_1") (pintype "passive"))
      (node (ref "U14") (pin "9") (pinfunction "GND_9") (pintype "power_in"))
    )
    (net (code "96") (name "Net-(SJ10-1)") (class "Default")
      (node (ref "SJ10") (pin "P$1") (pinfunction "1_P$1") (pintype "passive"))
      (node (ref "SJ11") (pin "P$1") (pinfunction "1_P$1") (pintype "passive"))
      (node (ref "SJ12") (pin "P$1") (pinfunction "1_P$1") (pintype "passive"))
      (node (ref "U14") (pin "10") (pinfunction "CD+_10") (pintype "passive"))
    )
    (net (code "97") (name "Net-(SJ13-1)") (class "Default")
      (node (ref "SJ13") (pin "P$1") (pinfunction "1_P$1") (pintype "passive"))
      (node (ref "U$1") (pin "PB14") (pinfunction "PB14_PB14") (pintype "bidirectional"))
    )
    (net (code "98") (name "Net-(SJ14-1)") (class "Default")
      (node (ref "SJ14") (pin "P$1") (pinfunction "1_P$1") (pintype "passive"))
      (node (ref "U$1") (pin "VIN2") (pinfunction "VIN2_VIN2") (pintype "power_in"))
    )
    (net (code "99") (name "Net-(SJ16-2)") (class "Default")
      (node (ref "JP2") (pin "2") (pinfunction "2_2") (pintype "passive"))
      (node (ref "SJ15") (pin "2") (pinfunction "2_2") (pintype "passive"))
      (node (ref "SJ16") (pin "P$2") (pinfunction "2_P$2") (pintype "passive"))
    )
    (net (code "100") (name "Net-(SJ18-2)") (class "Default")
      (node (ref "SJ18") (pin "P$2") (pinfunction "2_P$2") (pintype "passive"))
      (node (ref "U7") (pin "5") (pinfunction "VREF_5") (pintype "output"))
      (node (ref "U7B") (pin "5") (pinfunction "VREF_5") (pintype "bidirectional"))
    )
    (net (code "101") (name "Net-(U3A-O)") (class "Default")
      (node (ref "PORTC") (pin "1") (pinfunction "1_1") (pintype "passive"))
      (node (ref "U3") (pin "7") (pinfunction "O_7") (pintype "output"))
      (node (ref "U9") (pin "7") (pinfunction "OUT_7") (pintype "output"))
      (node (ref "X3") (pin "1") (pinfunction "1_1") (pintype "passive"))
    )
    (net (code "102") (name "Net-(U3B-O)") (class "Default")
      (node (ref "PORTC") (pin "2") (pinfunction "2_2") (pintype "passive"))
      (node (ref "U3") (pin "5") (pinfunction "O_5") (pintype "output"))
      (node (ref "U9") (pin "8") (pinfunction "OUT_8") (pintype "output"))
      (node (ref "X3") (pin "2") (pinfunction "2_2") (pintype "passive"))
    )
    (net (code "103") (name "Net-(U4A-O)") (class "Default")
      (node (ref "PORTC") (pin "4") (pinfunction "4_4") (pintype "passive"))
      (node (ref "U4") (pin "7") (pinfunction "O_7") (pintype "output"))
      (node (ref "U9") (pin "14") (pinfunction "OUT_14") (pintype "output"))
      (node (ref "X3") (pin "4") (pinfunction "4_4") (pintype "passive"))
    )
    (net (code "104") (name "Net-(U4B-O)") (class "Default")
      (node (ref "PORTC") (pin "3") (pinfunction "3_3") (pintype "passive"))
      (node (ref "U4") (pin "5") (pinfunction "O_5") (pintype "output"))
      (node (ref "U9") (pin "1") (pinfunction "OUT_1") (pintype "output"))
      (node (ref "X3") (pin "3") (pinfunction "3_3") (pintype "passive"))
    )
    (net (code "105") (name "Net-(U7-RS)") (class "Default")
      (node (ref "R61") (pin "1") (pinfunction "1_1") (pintype "passive"))
      (node (ref "U7") (pin "8") (pinfunction "RS_8") (pintype "input"))
      (node (ref "U7B") (pin "8") (pinfunction "RS_8") (pintype "bidirectional"))
    )
    (net (code "106") (name "Net-(U8-VOUT)") (class "Default")
      (node (ref "D1") (pin "C") (pinfunction "C_C") (pintype "passive"))
      (node (ref "D3") (pin "C") (pinfunction "C_C") (pintype "passive"))
      (node (ref "L1") (pin "2") (pinfunction "2_2") (pintype "passive"))
      (node (ref "U8") (pin "2") (pinfunction "VOUT_2") (pintype "bidirectional"))
      (node (ref "U8B") (pin "7") (pinfunction "OUT_7") (pintype "passive"))
    )
    (net (code "107") (name "Net-(U10A--IN)") (class "Default")
      (node (ref "R1") (pin "1") (pinfunction "1_1") (pintype "passive"))
      (node (ref "R2") (pin "2") (pinfunction "2_2") (pintype "passive"))
      (node (ref "U10") (pin "13") (pinfunction "-IN_13") (pintype "input"))
      (node (ref "U10") (pin "2") (pinfunction "-IN_2") (pintype "input"))
      (node (ref "U10") (pin "6") (pinfunction "-IN_6") (pintype "input"))
      (node (ref "U10") (pin "9") (pinfunction "-IN_9") (pintype "input"))
      (node (ref "U9") (pin "13") (pinfunction "-IN_13") (pintype "input"))
      (node (ref "U9") (pin "2") (pinfunction "-IN_2") (pintype "input"))
      (node (ref "U9") (pin "6") (pinfunction "-IN_6") (pintype "input"))
      (node (ref "U9") (pin "9") (pinfunction "-IN_9") (pintype "input"))
    )
    (net (code "108") (name "Net-(U10A-OUT)") (class "Default")
      (node (ref "PORTC") (pin "9") (pinfunction "9_9") (pintype "passive"))
      (node (ref "U10") (pin "1") (pinfunction "OUT_1") (pintype "output"))
      (node (ref "U6") (pin "5") (pinfunction "O_5") (pintype "output"))
      (node (ref "X3") (pin "7") (pinfunction "7_7") (pintype "passive"))
    )
    (net (code "109") (name "Net-(U10B-OUT)") (class "Default")
      (node (ref "PORTC") (pin "7") (pinfunction "7_7") (pintype "passive"))
      (node (ref "U10") (pin "7") (pinfunction "OUT_7") (pintype "output"))
      (node (ref "U5") (pin "7") (pinfunction "O_7") (pintype "output"))
      (node (ref "X3") (pin "5") (pinfunction "5_5") (pintype "passive"))
    )
    (net (code "110") (name "Net-(U10C-OUT)") (class "Default")
      (node (ref "PORTC") (pin "8") (pinfunction "8_8") (pintype "passive"))
      (node (ref "U10") (pin "8") (pinfunction "OUT_8") (pintype "output"))
      (node (ref "U5") (pin "5") (pinfunction "O_5") (pintype "output"))
      (node (ref "X3") (pin "6") (pinfunction "6_6") (pintype "passive"))
    )
    (net (code "111") (name "Net-(U10D-OUT)") (class "Default")
      (node (ref "PORTC") (pin "10") (pinfunction "10_10") (pintype "passive"))
      (node (ref "U10") (pin "14") (pinfunction "OUT_14") (pintype "output"))
      (node (ref "U6") (pin "7") (pinfunction "O_7") (pintype "output"))
      (node (ref "X3") (pin "8") (pinfunction "8_8") (pintype "passive"))
    )
    (net (code "112") (name "Net-(U11A-QA)") (class "Default")
      (node (ref "R3") (pin "1") (pinfunction "1_1") (pintype "passive"))
      (node (ref "U11") (pin "15") (pinfunction "QA_15") (pintype "tri_state"))
      (node (ref "U12") (pin "1") (pinfunction "I1_1") (pintype "input"))
    )
    (net (code "113") (name "Net-(U11A-QB)") (class "Default")
      (node (ref "R4") (pin "1") (pinfunction "1_1") (pintype "passive"))
      (node (ref "U11") (pin "1") (pinfunction "QB_1") (pintype "tri_state"))
      (node (ref "U12") (pin "2") (pinfunction "I2_2") (pintype "input"))
    )
    (net (code "114") (name "Net-(U11A-QC)") (class "Default")
      (node (ref "R5") (pin "1") (pinfunction "1_1") (pintype "passive"))
      (node (ref "U11") (pin "2") (pinfunction "QC_2") (pintype "tri_state"))
      (node (ref "U12") (pin "3") (pinfunction "I3_3") (pintype "input"))
    )
    (net (code "115") (name "Net-(U11A-QD)") (class "Default")
      (node (ref "R6") (pin "1") (pinfunction "1_1") (pintype "passive"))
      (node (ref "U11") (pin "3") (pinfunction "QD_3") (pintype "tri_state"))
      (node (ref "U12") (pin "4") (pinfunction "I4_4") (pintype "input"))
    )
    (net (code "116") (name "Net-(U11A-QE)") (class "Default")
      (node (ref "R7") (pin "1") (pinfunction "1_1") (pintype "passive"))
      (node (ref "U11") (pin "4") (pinfunction "QE_4") (pintype "tri_state"))
      (node (ref "U12") (pin "5") (pinfunction "I5_5") (pintype "input"))
    )
    (net (code "117") (name "Net-(U11A-QF)") (class "Default")
      (node (ref "R8") (pin "1") (pinfunction "1_1") (pintype "passive"))
      (node (ref "U11") (pin "5") (pinfunction "QF_5") (pintype "tri_state"))
      (node (ref "U12") (pin "6") (pinfunction "I6_6") (pintype "input"))
    )
    (net (code "118") (name "Net-(U11A-QG)") (class "Default")
      (node (ref "R9") (pin "1") (pinfunction "1_1") (pintype "passive"))
      (node (ref "U11") (pin "6") (pinfunction "QG_6") (pintype "tri_state"))
      (node (ref "U12") (pin "7") (pinfunction "I7_7") (pintype "input"))
    )
    (net (code "119") (name "Net-(U11A-QH)") (class "Default")
      (node (ref "R10") (pin "1") (pinfunction "1_1") (pintype "passive"))
      (node (ref "U11") (pin "7") (pinfunction "QH_7") (pintype "tri_state"))
      (node (ref "U12") (pin "8") (pinfunction "I8_8") (pintype "input"))
    )
    (net (code "120") (name "Net-(U13A-QA)") (class "Default")
      (node (ref "R11") (pin "1") (pinfunction "1_1") (pintype "passive"))
      (node (ref "U13") (pin "15") (pinfunction "QA_15") (pintype "tri_state"))
      (node (ref "U14") (pin "1") (pinfunction "I1_1") (pintype "input"))
    )
    (net (code "121") (name "Net-(U13A-QB)") (class "Default")
      (node (ref "R12") (pin "1") (pinfunction "1_1") (pintype "passive"))
      (node (ref "U13") (pin "1") (pinfunction "QB_1") (pintype "tri_state"))
      (node (ref "U14") (pin "2") (pinfunction "I2_2") (pintype "input"))
    )
    (net (code "122") (name "Net-(U13A-QC)") (class "Default")
      (node (ref "R13") (pin "1") (pinfunction "1_1") (pintype "passive"))
      (node (ref "U13") (pin "2") (pinfunction "QC_2") (pintype "tri_state"))
      (node (ref "U14") (pin "3") (pinfunction "I3_3") (pintype "input"))
    )
    (net (code "123") (name "Net-(U13A-QD)") (class "Default")
      (node (ref "R14") (pin "1") (pinfunction "1_1") (pintype "passive"))
      (node (ref "U13") (pin "3") (pinfunction "QD_3") (pintype "tri_state"))
      (node (ref "U14") (pin "4") (pinfunction "I4_4") (pintype "input"))
    )
    (net (code "124") (name "Net-(U13A-QE)") (class "Default")
      (node (ref "R15") (pin "1") (pinfunction "1_1") (pintype "passive"))
      (node (ref "U13") (pin "4") (pinfunction "QE_4") (pintype "tri_state"))
      (node (ref "U14") (pin "5") (pinfunction "I5_5") (pintype "input"))
    )
    (net (code "125") (name "Net-(U13A-QF)") (class "Default")
      (node (ref "R16") (pin "1") (pinfunction "1_1") (pintype "passive"))
      (node (ref "U13") (pin "5") (pinfunction "QF_5") (pintype "tri_state"))
      (node (ref "U14") (pin "6") (pinfunction "I6_6") (pintype "input"))
    )
    (net (code "126") (name "Net-(U13A-QG)") (class "Default")
      (node (ref "R17") (pin "1") (pinfunction "1_1") (pintype "passive"))
      (node (ref "U13") (pin "6") (pinfunction "QG_6") (pintype "tri_state"))
      (node (ref "U14") (pin "7") (pinfunction "I7_7") (pintype "input"))
    )
    (net (code "127") (name "Net-(U13A-QH)") (class "Default")
      (node (ref "R18") (pin "1") (pinfunction "1_1") (pintype "passive"))
      (node (ref "U13") (pin "7") (pinfunction "QH_7") (pintype "tri_state"))
      (node (ref "U14") (pin "8") (pinfunction "I8_8") (pintype "input"))
    )
    (net (code "128") (name "OLAT") (class "Default")
      (node (ref "R21") (pin "1") (pinfunction "1_1") (pintype "passive"))
      (node (ref "U$1") (pin "PA8") (pinfunction "PA8_PA8") (pintype "bidirectional"))
      (node (ref "U11") (pin "12") (pinfunction "RCK_12") (pintype "input"))
      (node (ref "U13") (pin "12") (pinfunction "RCK_12") (pintype "input"))
    )
    (net (code "129") (name "SCK") (class "Default")
      (node (ref "JP2") (pin "3") (pinfunction "3_3") (pintype "passive"))
      (node (ref "R19") (pin "1") (pinfunction "1_1") (pintype "passive"))
      (node (ref "U$1") (pin "PB3") (pinfunction "PB3_PB3") (pintype "bidirectional"))
      (node (ref "U11") (pin "11") (pinfunction "SCK_11") (pintype "input"))
      (node (ref "U13") (pin "11") (pinfunction "SCK_11") (pintype "input"))
    )
    (net (code "130") (name "SCK2") (class "Default")
      (node (ref "U$1") (pin "PB10") (pinfunction "PB10_PB10") (pintype "bidirectional"))
      (node (ref "U1") (pin "7") (pinfunction "CLK_7") (pintype "input"))
      (node (ref "U2") (pin "7") (pinfunction "CLK_7") (pintype "input"))
    )
    (net (code "131") (name "SLNK1") (class "Default")
      (node (ref "SJ17") (pin "P$1") (pinfunction "1_P$1") (pintype "passive"))
      (node (ref "U11") (pin "9") (pinfunction "QH*_9") (pintype "tri_state"))
      (node (ref "U13") (pin "14") (pinfunction "SER_14") (pintype "input"))
    )
    (net (code "132") (name "SLNK2") (class "Default")
      (node (ref "SJ16") (pin "P$1") (pinfunction "1_P$1") (pintype "passive"))
      (node (ref "U13") (pin "9") (pinfunction "QH*_9") (pintype "tri_state"))
    )
    (net (code "133") (name "SLNK3") (class "Default")
      (node (ref "SJ19") (pin "P$1") (pinfunction "1_P$1") (pintype "passive"))
      (node (ref "U1") (pin "13") (pinfunction "QH_13") (pintype "output"))
      (node (ref "U2") (pin "1") (pinfunction "SER_1") (pintype "input"))
    )
    (net (code "134") (name "SRV1") (class "Default")
      (node (ref "JP5") (pin "2") (pinfunction "2_2") (pintype "passive"))
      (node (ref "R24") (pin "2") (pinfunction "2_2") (pintype "passive"))
      (node (ref "U$1") (pin "PC9") (pinfunction "PC9_PC9") (pintype "bidirectional"))
    )
    (net (code "135") (name "SRV2") (class "Default")
      (node (ref "JP5") (pin "1") (pinfunction "1_1") (pintype "passive"))
      (node (ref "R25") (pin "2") (pinfunction "2_2") (pintype "passive"))
      (node (ref "U$1") (pin "PC7") (pinfunction "PC7_PC7") (pintype "bidirectional"))
    )
    (net (code "136") (name "SRV3") (class "Default")
      (node (ref "JP6") (pin "2") (pinfunction "2_2") (pintype "passive"))
      (node (ref "R26") (pin "2") (pinfunction "2_2") (pintype "passive"))
      (node (ref "U$1") (pin "PC8") (pinfunction "PC8_PC8") (pintype "bidirectional"))
    )
    (net (code "137") (name "SRV4") (class "Default")
      (node (ref "JP6") (pin "1") (pinfunction "1_1") (pintype "passive"))
      (node (ref "R27") (pin "2") (pinfunction "2_2") (pintype "passive"))
      (node (ref "U$1") (pin "PC6") (pinfunction "PC6_PC6") (pintype "bidirectional"))
    )
    (net (code "138") (name "SRV5") (class "Default")
      (node (ref "JP7") (pin "2") (pinfunction "2_2") (pintype "passive"))
      (node (ref "R64") (pin "2") (pinfunction "2_2") (pintype "passive"))
      (node (ref "U$1") (pin "PF1-PH1") (pinfunction "PF1-PH1_PF1-PH1") (pintype "bidirectional"))
    )
    (net (code "139") (name "SRV6") (class "Default")
      (node (ref "JP7") (pin "1") (pinfunction "1_1") (pintype "passive"))
      (node (ref "R65") (pin "2") (pinfunction "2_2") (pintype "passive"))
      (node (ref "U$1") (pin "PA15") (pinfunction "PA15_PA15") (pintype "bidirectional"))
    )
    (net (code "140") (name "SRV7") (class "Default")
      (node (ref "JP8") (pin "2") (pinfunction "2_2") (pintype "passive"))
      (node (ref "R66") (pin "2") (pinfunction "2_2") (pintype "passive"))
      (node (ref "U$1") (pin "PC12") (pinfunction "PC12_PC12") (pintype "bidirectional"))
    )
    (net (code "141") (name "SRV8") (class "Default")
      (node (ref "JP8") (pin "1") (pinfunction "1_1") (pintype "passive"))
      (node (ref "R67") (pin "2") (pinfunction "2_2") (pintype "passive"))
      (node (ref "U$1") (pin "PD2") (pinfunction "PD2_PD2") (pintype "bidirectional"))
    )
    (net (code "142") (name "TDRV1") (class "Default")
      (node (ref "U$1") (pin "PB12") (pinfunction "PB12_PB12") (pintype "bidirectional"))
      (node (ref "U10") (pin "12") (pinfunction "+IN_12") (pintype "input"))
      (node (ref "U6") (pin "2") (pinfunction "I_2") (pintype "input"))
    )
    (net (code "143") (name "TDRV2") (class "Default")
      (node (ref "U$1") (pin "PB2") (pinfunction "PB2_PB2") (pintype "bidirectional"))
      (node (ref "U10") (pin "3") (pinfunction "+IN_3") (pintype "input"))
      (node (ref "U6") (pin "4") (pinfunction "I_4") (pintype "input"))
    )
    (net (code "144") (name "TDRV3") (class "Default")
      (node (ref "U$1") (pin "PB15") (pinfunction "PB15_PB15") (pintype "bidirectional"))
      (node (ref "U10") (pin "10") (pinfunction "+IN_10") (pintype "input"))
      (node (ref "U5") (pin "4") (pinfunction "I_4") (pintype "input"))
    )
    (net (code "145") (name "TDRV4") (class "Default")
      (node (ref "U$1") (pin "PB1") (pinfunction "PB1_PB1") (pintype "bidirectional"))
      (node (ref "U10") (pin "5") (pinfunction "+IN_5") (pintype "input"))
      (node (ref "U5") (pin "2") (pinfunction "I_2") (pintype "input"))
    )
    (net (code "146") (name "TDRV5") (class "Default")
      (node (ref "U$1") (pin "PA0") (pinfunction "PA0_PA0") (pintype "bidirectional"))
      (node (ref "U4") (pin "2") (pinfunction "I_2") (pintype "input"))
      (node (ref "U9") (pin "12") (pinfunction "+IN_12") (pintype "input"))
    )
    (net (code "147") (name "TDRV6") (class "Default")
      (node (ref "U$1") (pin "PA4") (pinfunction "PA4_PA4") (pintype "bidirectional"))
      (node (ref "U4") (pin "4") (pinfunction "I_4") (pintype "input"))
      (node (ref "U9") (pin "3") (pinfunction "+IN_3") (pintype "input"))
    )
    (net (code "148") (name "TDRV7") (class "Default")
      (node (ref "U$1") (pin "PC3") (pinfunction "PC3_PC3") (pintype "bidirectional"))
      (node (ref "U3") (pin "4") (pinfunction "I_4") (pintype "input"))
      (node (ref "U9") (pin "10") (pinfunction "+IN_10") (pintype "input"))
    )
    (net (code "149") (name "TDRV8") (class "Default")
      (node (ref "U$1") (pin "PC0") (pinfunction "PC0_PC0") (pintype "bidirectional"))
      (node (ref "U3") (pin "2") (pinfunction "I_2") (pintype "input"))
      (node (ref "U9") (pin "5") (pinfunction "+IN_5") (pintype "input"))
    )
    (net (code "150") (name "V+") (class "Default")
      (node (ref "C1") (pin "1") (pinfunction "1_1") (pintype "passive"))
      (node (ref "C2") (pin "+") (pinfunction "+_+") (pintype "passive"))
      (node (ref "L1") (pin "1") (pinfunction "1_1") (pintype "passive"))
      (node (ref "U$1") (pin "E5V") (pinfunction "E5V_E5V") (pintype "power_in"))
      (node (ref "U8") (pin "3") (pinfunction "FB_3") (pintype "bidirectional"))
      (node (ref "U8B") (pin "1") (pinfunction "FB_1") (pintype "input"))
    )
    (net (code "151") (name "unconnected-(H1-MOUNT-PadB3,3)") (class "Default")
      (node (ref "H1") (pin "B3,3") (pinfunction "MOUNT_B3,3") (pintype "passive"))
    )
    (net (code "152") (name "unconnected-(H2-MOUNT-PadB3,3)") (class "Default")
      (node (ref "H2") (pin "B3,3") (pinfunction "MOUNT_B3,3") (pintype "passive"))
    )
    (net (code "153") (name "unconnected-(H3-MOUNT-PadB3,3)") (class "Default")
      (node (ref "H3") (pin "B3,3") (pinfunction "MOUNT_B3,3") (pintype "passive"))
    )
    (net (code "154") (name "unconnected-(H4-MOUNT-PadB3,3)") (class "Default")
      (node (ref "H4") (pin "B3,3") (pinfunction "MOUNT_B3,3") (pintype "passive"))
    )
    (net (code "155") (name "unconnected-(U$1-PadBOOT0)") (class "Default")
      (node (ref "U$1") (pin "BOOT0") (pinfunction "BOOT0_BOOT0") (pintype "bidirectional"))
    )
    (net (code "156") (name "unconnected-(U$1-PadIOREF2)") (class "Default")
      (node (ref "U$1") (pin "IOREF2") (pinfunction "IOREF2_IOREF2") (pintype "input"))
    )
    (net (code "157") (name "unconnected-(U$1-PadNC1-PF7)") (class "Default")
      (node (ref "U$1") (pin "NC1-PF7") (pinfunction "NC1-PF7_NC1-PF7") (pintype "bidirectional"))
    )
    (net (code "158") (name "unconnected-(U$1-PadNC2-PF6)") (class "Default")
      (node (ref "U$1") (pin "NC2-PF6") (pinfunction "NC2-PF6_NC2-PF6") (pintype "bidirectional"))
    )
    (net (code "159") (name "unconnected-(U$1-PadNC3)") (class "Default")
      (node (ref "U$1") (pin "NC3") (pinfunction "NC3_NC3") (pintype "no_connect"))
    )
    (net (code "160") (name "unconnected-(U$1-PadNC4)") (class "Default")
      (node (ref "U$1") (pin "NC4") (pinfunction "NC4_NC4") (pintype "no_connect"))
    )
    (net (code "161") (name "unconnected-(U$1-PadNC5-PD8)") (class "Default")
      (node (ref "U$1") (pin "NC5-PD8") (pinfunction "NC5-PD8_NC5-PD8") (pintype "bidirectional"))
    )
    (net (code "162") (name "unconnected-(U$1-PadNC6-PB11)") (class "Default")
      (node (ref "U$1") (pin "NC6-PB11") (pinfunction "NC6-PB11_NC6-PB11") (pintype "no_connect"))
    )
    (net (code "163") (name "unconnected-(U$1-PadNC7-PF5)") (class "Default")
      (node (ref "U$1") (pin "NC7-PF5") (pinfunction "NC7-PF5_NC7-PF5") (pintype "bidirectional"))
    )
    (net (code "164") (name "unconnected-(U$1-PadNC8-PF4)") (class "Default")
      (node (ref "U$1") (pin "NC8-PF4") (pinfunction "NC8-PF4_NC8-PF4") (pintype "bidirectional"))
    )
    (net (code "165") (name "unconnected-(U$1-PadNRESET)") (class "Default")
      (node (ref "U$1") (pin "NRESET") (pinfunction "NRESET_NRESET") (pintype "input"))
    )
    (net (code "166") (name "unconnected-(U$1-PadPA1)") (class "Default")
      (node (ref "U$1") (pin "PA1") (pinfunction "PA1_PA1") (pintype "bidirectional"))
    )
    (net (code "167") (name "unconnected-(U$1-PadPA2)") (class "Default")
      (node (ref "U$1") (pin "PA2") (pinfunction "PA2_PA2") (pintype "bidirectional"))
    )
    (net (code "168") (name "unconnected-(U$1-PadPA3)") (class "Default")
      (node (ref "U$1") (pin "PA3") (pinfunction "PA3_PA3") (pintype "bidirectional"))
    )
    (net (code "169") (name "unconnected-(U$1-PadPA5)") (class "Default")
      (node (ref "U$1") (pin "PA5") (pinfunction "PA5_PA5") (pintype "bidirectional"))
    )
    (net (code "170") (name "unconnected-(U$1-PadPA7)") (class "Default")
      (node (ref "U$1") (pin "PA7") (pinfunction "PA7_PA7") (pintype "bidirectional"))
    )
    (net (code "171") (name "unconnected-(U$1-PadPA9)") (class "Default")
      (node (ref "U$1") (pin "PA9") (pinfunction "PA9_PA9") (pintype "bidirectional"))
    )
    (net (code "172") (name "unconnected-(U$1-PadPA10)") (class "Default")
      (node (ref "U$1") (pin "PA10") (pinfunction "PA10_PA10") (pintype "bidirectional"))
    )
    (net (code "173") (name "unconnected-(U$1-PadPA11)") (class "Default")
      (node (ref "U$1") (pin "PA11") (pinfunction "PA11_PA11") (pintype "bidirectional"))
    )
    (net (code "174") (name "unconnected-(U$1-PadPA12)") (class "Default")
      (node (ref "U$1") (pin "PA12") (pinfunction "PA12_PA12") (pintype "bidirectional"))
    )
    (net (code "175") (name "unconnected-(U$1-PadPA13)") (class "Default")
      (node (ref "U$1") (pin "PA13") (pinfunction "PA13_PA13") (pintype "bidirectional"))
    )
    (net (code "176") (name "unconnected-(U$1-PadPA14)") (class "Default")
      (node (ref "U$1") (pin "PA14") (pinfunction "PA14_PA14") (pintype "bidirectional"))
    )
    (net (code "177") (name "unconnected-(U$1-PadPB0)") (class "Default")
      (node (ref "U$1") (pin "PB0") (pinfunction "PB0_PB0") (pintype "bidirectional"))
    )
    (net (code "178") (name "unconnected-(U$1-PadPB13)") (class "Default")
      (node (ref "U$1") (pin "PB13") (pinfunction "PB13_PB13") (pintype "bidirectional"))
    )
    (net (code "179") (name "unconnected-(U$1-PadPC1)") (class "Default")
      (node (ref "U$1") (pin "PC1") (pinfunction "PC1_PC1") (pintype "bidirectional"))
    )
    (net (code "180") (name "unconnected-(U$1-PadPC4)") (class "Default")
      (node (ref "U$1") (pin "PC4") (pinfunction "PC4_PC4") (pintype "bidirectional"))
    )
    (net (code "181") (name "unconnected-(U$1-PadPC5)") (class "Default")
      (node (ref "U$1") (pin "PC5") (pinfunction "PC5_PC5") (pintype "bidirectional"))
    )
    (net (code "182") (name "unconnected-(U$1-PadPC13)") (class "Default")
      (node (ref "U$1") (pin "PC13") (pinfunction "PC13_PC13") (pintype "bidirectional"))
    )
    (net (code "183") (name "unconnected-(U$1-PadPC14)") (class "Default")
      (node (ref "U$1") (pin "PC14") (pinfunction "PC14_PC14") (pintype "bidirectional"))
    )
    (net (code "184") (name "unconnected-(U$1-PadPC15)") (class "Default")
      (node (ref "U$1") (pin "PC15") (pinfunction "PC15_PC15") (pintype "bidirectional"))
    )
    (net (code "185") (name "unconnected-(U$1-PadPF0-PH0)") (class "Default")
      (node (ref "U$1") (pin "PF0-PH0") (pinfunction "PF0-PH0_PF0-PH0") (pintype "bidirectional"))
    )
  )
)
